# Schematic_01.net
KiCad netlist of a schematic drawn in EAGLE
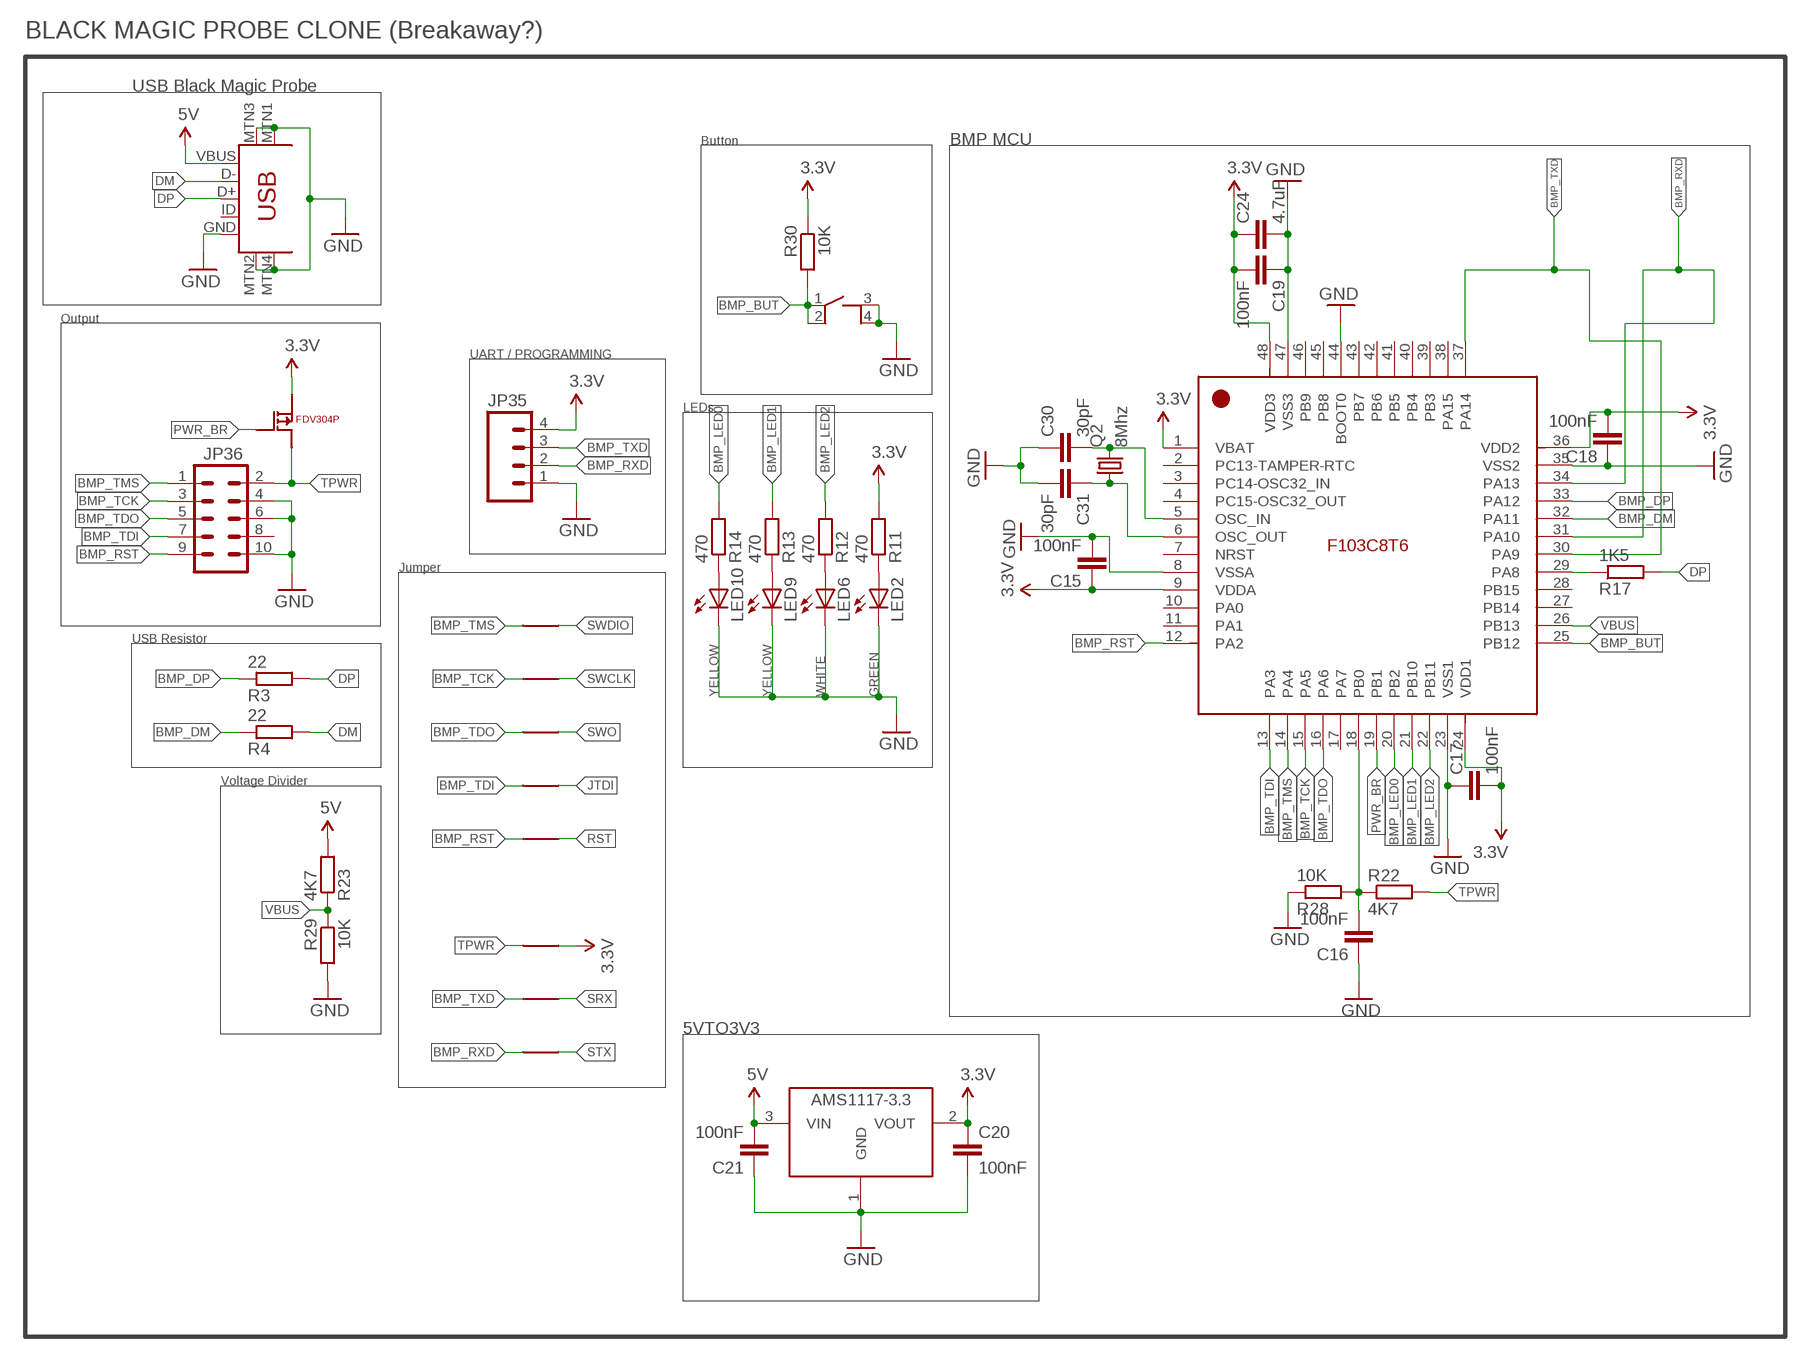
[diagram p0: schematic, sheet 1, part 1 of 2]
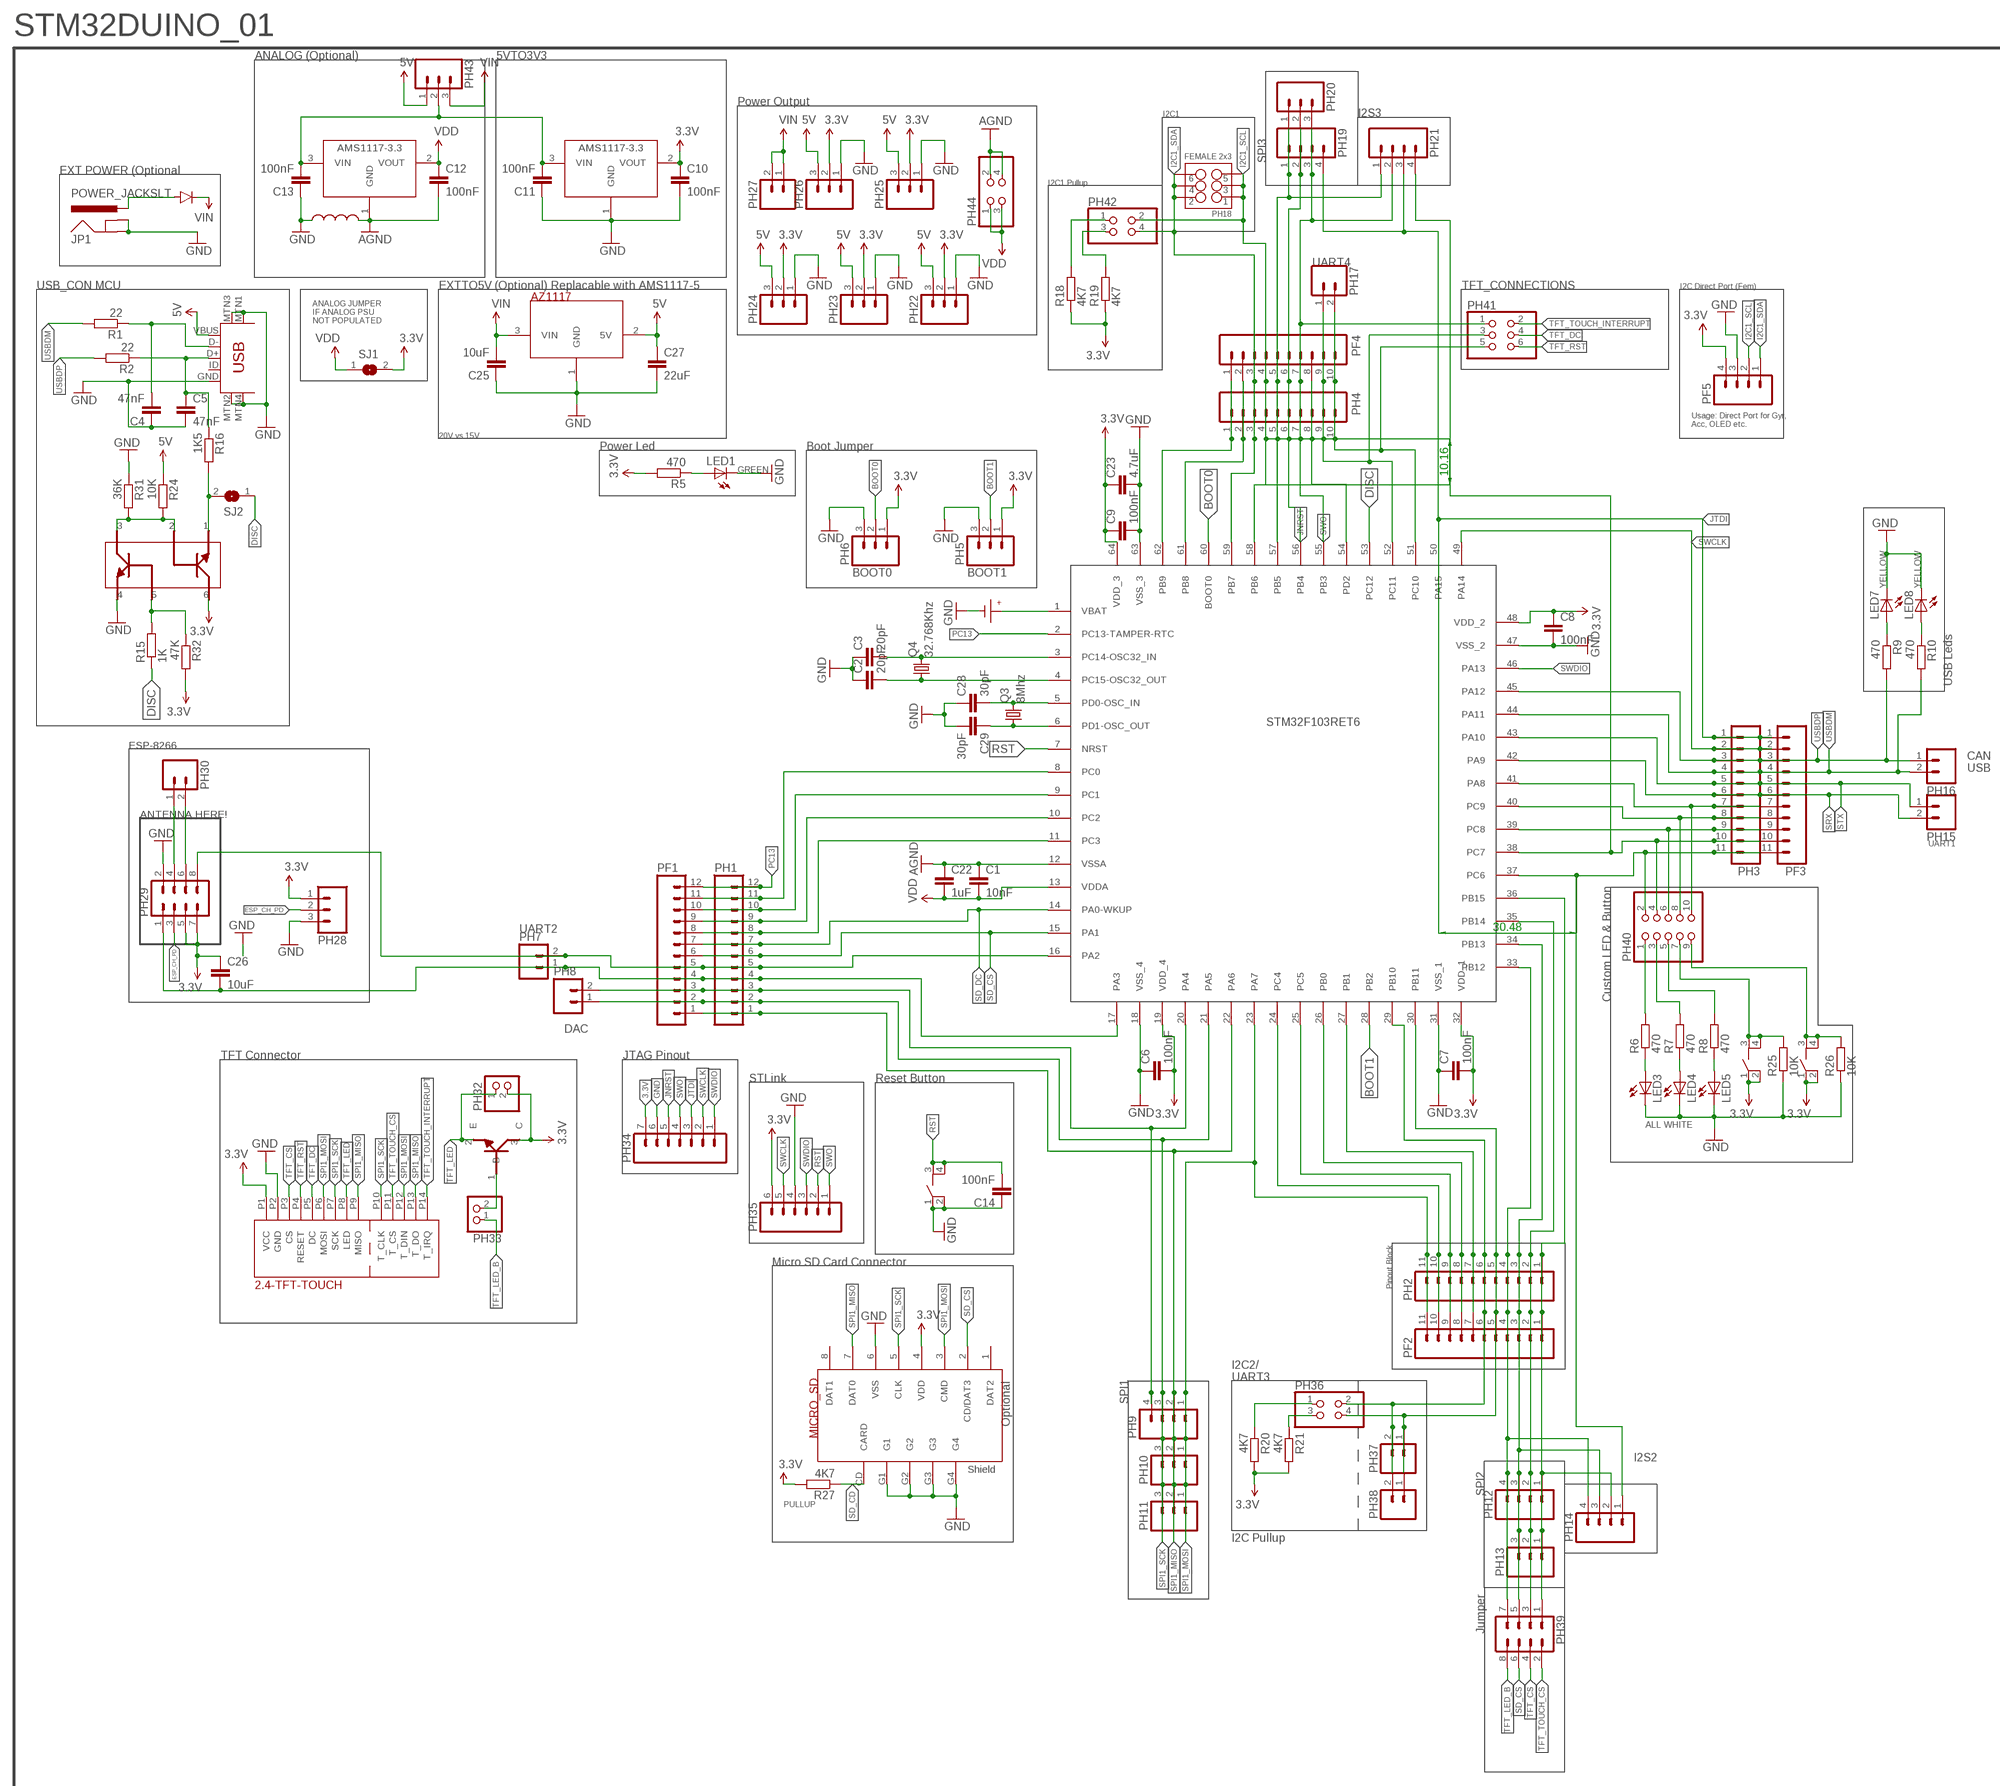
[diagram p1: schematic, sheet 1, part 2 of 2]

(export (version "E")
  (design (tool "Eeschema 10.0.6"))
  (components
    (comp (ref "C1")
      (value "10nF")
      (footprint "eagle-import:C0805K")
      (libsource (lib "eagle-import") (part "C-EUC0805K"))
    )
    (comp (ref "C2")
      (value "20pF")
      (footprint "eagle-import:C0805K")
      (libsource (lib "eagle-import") (part "C-EUC0805K"))
    )
    (comp (ref "C3")
      (value "20pF")
      (footprint "eagle-import:C0805K")
      (libsource (lib "eagle-import") (part "C-EUC0805K"))
    )
    (comp (ref "C4")
      (value "47nF")
      (footprint "eagle-import:C0805K")
      (libsource (lib "eagle-import") (part "C-EUC0805K"))
    )
    (comp (ref "C5")
      (value "47nF")
      (footprint "eagle-import:C0805K")
      (libsource (lib "eagle-import") (part "C-EUC0805K"))
    )
    (comp (ref "C6")
      (value "100nF")
      (footprint "eagle-import:C0805K")
      (libsource (lib "eagle-import") (part "C-EUC0805K"))
    )
    (comp (ref "C7")
      (value "100nF")
      (footprint "eagle-import:C0805K")
      (libsource (lib "eagle-import") (part "C-EUC0805K"))
    )
    (comp (ref "C8")
      (value "100nF")
      (footprint "eagle-import:C0805K")
      (libsource (lib "eagle-import") (part "C-EUC0805K"))
    )
    (comp (ref "C9")
      (value "100nF")
      (footprint "eagle-import:C0805K")
      (libsource (lib "eagle-import") (part "C-EUC0805K"))
    )
    (comp (ref "C10")
      (value "100nF")
      (footprint "eagle-import:C0805K")
      (libsource (lib "eagle-import") (part "C-EUC0805K"))
    )
    (comp (ref "C11")
      (value "100nF")
      (footprint "eagle-import:C0805K")
      (libsource (lib "eagle-import") (part "C-EUC0805K"))
    )
    (comp (ref "C12")
      (value "100nF")
      (footprint "eagle-import:C0805K")
      (libsource (lib "eagle-import") (part "C-EUC0805K"))
    )
    (comp (ref "C13")
      (value "100nF")
      (footprint "eagle-import:C0805K")
      (libsource (lib "eagle-import") (part "C-EUC0805K"))
    )
    (comp (ref "C14")
      (value "100nF")
      (footprint "eagle-import:C0805K")
      (libsource (lib "eagle-import") (part "C-EUC0805K"))
    )
    (comp (ref "C15")
      (value "100nF")
      (footprint "eagle-import:C0805K")
      (libsource (lib "eagle-import") (part "C-EUC0805K"))
    )
    (comp (ref "C16")
      (value "100nF")
      (footprint "eagle-import:C0805K")
      (libsource (lib "eagle-import") (part "C-EUC0805K"))
    )
    (comp (ref "C17")
      (value "100nF")
      (footprint "eagle-import:C0805K")
      (libsource (lib "eagle-import") (part "C-EUC0805K"))
    )
    (comp (ref "C18")
      (value "100nF")
      (footprint "eagle-import:C0805K")
      (libsource (lib "eagle-import") (part "C-EUC0805K"))
    )
    (comp (ref "C19")
      (value "100nF")
      (footprint "eagle-import:C0805K")
      (libsource (lib "eagle-import") (part "C-EUC0805K"))
    )
    (comp (ref "C20")
      (value "100nF")
      (footprint "eagle-import:C0805K")
      (libsource (lib "eagle-import") (part "C-EUC0805K"))
    )
    (comp (ref "C21")
      (value "100nF")
      (footprint "eagle-import:C0805K")
      (libsource (lib "eagle-import") (part "C-EUC0805K"))
    )
    (comp (ref "C22")
      (value "1uF")
      (footprint "eagle-import:C0805K")
      (libsource (lib "eagle-import") (part "C-EUC0805K"))
    )
    (comp (ref "C23")
      (value "4.7uF")
      (footprint "eagle-import:C0805K")
      (libsource (lib "eagle-import") (part "C-EUC0805K"))
    )
    (comp (ref "C24")
      (value "4.7uF")
      (footprint "eagle-import:C0805K")
      (libsource (lib "eagle-import") (part "C-EUC0805K"))
    )
    (comp (ref "C25")
      (value "10uF")
      (footprint "eagle-import:C0805K")
      (libsource (lib "eagle-import") (part "C-EUC0805K"))
    )
    (comp (ref "C26")
      (value "10uF")
      (footprint "eagle-import:C0805K")
      (libsource (lib "eagle-import") (part "C-EUC0805K"))
    )
    (comp (ref "C27")
      (value "22uF")
      (footprint "eagle-import:C0805K")
      (libsource (lib "eagle-import") (part "C-EUC0805K"))
    )
    (comp (ref "C28")
      (value "30pF")
      (footprint "eagle-import:C0805K")
      (libsource (lib "eagle-import") (part "C-EUC0805K"))
    )
    (comp (ref "C29")
      (value "30pF")
      (footprint "eagle-import:C0805K")
      (libsource (lib "eagle-import") (part "C-EUC0805K"))
    )
    (comp (ref "C30")
      (value "30pF")
      (footprint "eagle-import:C0805K")
      (libsource (lib "eagle-import") (part "C-EUC0805K"))
    )
    (comp (ref "C31")
      (value "30pF")
      (footprint "eagle-import:C0805K")
      (libsource (lib "eagle-import") (part "C-EUC0805K"))
    )
    (comp (ref "FB")
      (value "SMD_FERRITE_BEAD")
      (footprint "eagle-import:0805")
      (libsource (lib "eagle-import") (part "SMD_FERRITE_BEAD"))
    )
    (comp (ref "JP1")
      (value "POWER_JACKSLT")
      (footprint "eagle-import:POWER_JACK_SLOT")
      (libsource (lib "eagle-import") (part "POWER_JACKSLT"))
    )
    (comp (ref "JP35")
      (value "M04PTH")
      (footprint "eagle-import:1X04")
      (libsource (lib "eagle-import") (part "M04PTH"))
    )
    (comp (ref "JP36")
      (value "M05X2PTH")
      (footprint "eagle-import:AVR_ICSP")
      (libsource (lib "eagle-import") (part "M05X2PTH"))
    )
    (comp (ref "LED1")
      (value "LEDCHIPLED_0805")
      (footprint "eagle-import:CHIPLED_0805")
      (libsource (lib "eagle-import") (part "LEDCHIPLED_0805"))
    )
    (comp (ref "LED2")
      (value "LEDCHIPLED_1206")
      (footprint "eagle-import:CHIPLED_1206")
      (libsource (lib "eagle-import") (part "LEDCHIPLED_1206"))
    )
    (comp (ref "LED3")
      (value "LEDCHIPLED_0805")
      (footprint "eagle-import:CHIPLED_0805")
      (libsource (lib "eagle-import") (part "LEDCHIPLED_0805"))
    )
    (comp (ref "LED4")
      (value "LEDCHIPLED_0805")
      (footprint "eagle-import:CHIPLED_0805")
      (libsource (lib "eagle-import") (part "LEDCHIPLED_0805"))
    )
    (comp (ref "LED5")
      (value "LEDCHIPLED_0805")
      (footprint "eagle-import:CHIPLED_0805")
      (libsource (lib "eagle-import") (part "LEDCHIPLED_0805"))
    )
    (comp (ref "LED6")
      (value "LEDCHIPLED_1206")
      (footprint "eagle-import:CHIPLED_1206")
      (libsource (lib "eagle-import") (part "LEDCHIPLED_1206"))
    )
    (comp (ref "LED7")
      (value "LEDCHIPLED_0805")
      (footprint "eagle-import:CHIPLED_0805")
      (libsource (lib "eagle-import") (part "LEDCHIPLED_0805"))
    )
    (comp (ref "LED8")
      (value "LEDCHIPLED_0805")
      (footprint "eagle-import:CHIPLED_0805")
      (libsource (lib "eagle-import") (part "LEDCHIPLED_0805"))
    )
    (comp (ref "LED9")
      (value "LEDCHIPLED_1206")
      (footprint "eagle-import:CHIPLED_1206")
      (libsource (lib "eagle-import") (part "LEDCHIPLED_1206"))
    )
    (comp (ref "LED10")
      (value "LEDCHIPLED_1206")
      (footprint "eagle-import:CHIPLED_1206")
      (libsource (lib "eagle-import") (part "LEDCHIPLED_1206"))
    )
    (comp (ref "PF1")
      (value "M12PTH")
      (footprint "eagle-import:1X12")
      (libsource (lib "eagle-import") (part "M12PTH"))
    )
    (comp (ref "PF2")
      (value "M11PTH")
      (footprint "eagle-import:1X11")
      (libsource (lib "eagle-import") (part "M11PTH"))
    )
    (comp (ref "PF3")
      (value "M11PTH")
      (footprint "eagle-import:1X11")
      (libsource (lib "eagle-import") (part "M11PTH"))
    )
    (comp (ref "PF4")
      (value "M10SILK_FEMALE_PTH")
      (footprint "eagle-import:1X10")
      (libsource (lib "eagle-import") (part "M10SILK_FEMALE_PTH"))
    )
    (comp (ref "PF5")
      (value "M04PTH")
      (footprint "eagle-import:1X04")
      (libsource (lib "eagle-import") (part "M04PTH"))
    )
    (comp (ref "PH1")
      (value "M12PTH")
      (footprint "eagle-import:1X12")
      (libsource (lib "eagle-import") (part "M12PTH"))
    )
    (comp (ref "PH2")
      (value "M11PTH")
      (footprint "eagle-import:1X11")
      (libsource (lib "eagle-import") (part "M11PTH"))
    )
    (comp (ref "PH3")
      (value "M11PTH")
      (footprint "eagle-import:1X11")
      (libsource (lib "eagle-import") (part "M11PTH"))
    )
    (comp (ref "PH4")
      (value "M10SILK_FEMALE_PTH")
      (footprint "eagle-import:1X10")
      (libsource (lib "eagle-import") (part "M10SILK_FEMALE_PTH"))
    )
    (comp (ref "PH5")
      (value "M03PTH")
      (footprint "eagle-import:1X03")
      (libsource (lib "eagle-import") (part "M03PTH"))
    )
    (comp (ref "PH6")
      (value "M03PTH")
      (footprint "eagle-import:1X03")
      (libsource (lib "eagle-import") (part "M03PTH"))
    )
    (comp (ref "PH7")
      (value "M02PTH")
      (footprint "eagle-import:1X02")
      (libsource (lib "eagle-import") (part "M02PTH"))
    )
    (comp (ref "PH8")
      (value "M02PTH")
      (footprint "eagle-import:1X02")
      (libsource (lib "eagle-import") (part "M02PTH"))
    )
    (comp (ref "PH9")
      (value "M04PTH")
      (footprint "eagle-import:1X04")
      (libsource (lib "eagle-import") (part "M04PTH"))
    )
    (comp (ref "PH10")
      (value "M03PTH")
      (footprint "eagle-import:1X03")
      (libsource (lib "eagle-import") (part "M03PTH"))
    )
    (comp (ref "PH11")
      (value "M03PTH")
      (footprint "eagle-import:1X03")
      (libsource (lib "eagle-import") (part "M03PTH"))
    )
    (comp (ref "PH12")
      (value "M04PTH")
      (footprint "eagle-import:1X04")
      (libsource (lib "eagle-import") (part "M04PTH"))
    )
    (comp (ref "PH13")
      (value "M03PTH")
      (footprint "eagle-import:1X03")
      (libsource (lib "eagle-import") (part "M03PTH"))
    )
    (comp (ref "PH14")
      (value "M04PTH")
      (footprint "eagle-import:1X04")
      (libsource (lib "eagle-import") (part "M04PTH"))
    )
    (comp (ref "PH15")
      (value "M02PTH")
      (footprint "eagle-import:1X02")
      (libsource (lib "eagle-import") (part "M02PTH"))
    )
    (comp (ref "PH16")
      (value "M02PTH")
      (footprint "eagle-import:1X02")
      (libsource (lib "eagle-import") (part "M02PTH"))
    )
    (comp (ref "PH17")
      (value "M02PTH")
      (footprint "eagle-import:1X02")
      (libsource (lib "eagle-import") (part "M02PTH"))
    )
    (comp (ref "PH18")
      (value "FEMALE 2x3")
      (footprint "eagle-import:2X3")
      (libsource (lib "eagle-import") (part "M03X2FEMALE"))
    )
    (comp (ref "PH19")
      (value "M04PTH")
      (footprint "eagle-import:1X04")
      (libsource (lib "eagle-import") (part "M04PTH"))
    )
    (comp (ref "PH20")
      (value "M03PTH")
      (footprint "eagle-import:1X03")
      (libsource (lib "eagle-import") (part "M03PTH"))
    )
    (comp (ref "PH21")
      (value "M04PTH")
      (footprint "eagle-import:1X04")
      (libsource (lib "eagle-import") (part "M04PTH"))
    )
    (comp (ref "PH22")
      (value "M03PTH")
      (footprint "eagle-import:1X03")
      (libsource (lib "eagle-import") (part "M03PTH"))
    )
    (comp (ref "PH23")
      (value "M03PTH")
      (footprint "eagle-import:1X03")
      (libsource (lib "eagle-import") (part "M03PTH"))
    )
    (comp (ref "PH24")
      (value "M03PTH")
      (footprint "eagle-import:1X03")
      (libsource (lib "eagle-import") (part "M03PTH"))
    )
    (comp (ref "PH25")
      (value "M03PTH")
      (footprint "eagle-import:1X03")
      (libsource (lib "eagle-import") (part "M03PTH"))
    )
    (comp (ref "PH26")
      (value "M03PTH")
      (footprint "eagle-import:1X03")
      (libsource (lib "eagle-import") (part "M03PTH"))
    )
    (comp (ref "PH27")
      (value "M02PTH")
      (footprint "eagle-import:1X02")
      (libsource (lib "eagle-import") (part "M02PTH"))
    )
    (comp (ref "PH28")
      (value "M03PTH")
      (footprint "eagle-import:1X03")
      (libsource (lib "eagle-import") (part "M03PTH"))
    )
    (comp (ref "PH29")
      (value "M04X2")
      (footprint "eagle-import:2X4")
      (libsource (lib "eagle-import") (part "M04X2"))
    )
    (comp (ref "PH30")
      (value "M02PTH")
      (footprint "eagle-import:1X02")
      (libsource (lib "eagle-import") (part "M02PTH"))
    )
    (comp (ref "PH31")
      (value "TFT-TOUCH")
      (footprint "eagle-import:TFT-TOUCH")
      (libsource (lib "eagle-import") (part "TFT-TOUCH"))
    )
    (comp (ref "PH32")
      (value "PINHD-1X2")
      (footprint "eagle-import:1X02")
      (libsource (lib "eagle-import") (part "PINHD-1X2"))
    )
    (comp (ref "PH33")
      (value "PINHD-1X2")
      (footprint "eagle-import:1X02")
      (libsource (lib "eagle-import") (part "PINHD-1X2"))
    )
    (comp (ref "PH34")
      (value "M07")
      (footprint "eagle-import:1X07")
      (libsource (lib "eagle-import") (part "M07"))
    )
    (comp (ref "PH35")
      (value "M06SILK_FEMALE_PTH")
      (footprint "eagle-import:1X06")
      (libsource (lib "eagle-import") (part "M06SILK_FEMALE_PTH"))
    )
    (comp (ref "PH36")
      (value "PINHD-2X2")
      (footprint "eagle-import:2X02")
      (libsource (lib "eagle-import") (part "PINHD-2X2"))
    )
    (comp (ref "PH37")
      (value "M02PTH")
      (footprint "eagle-import:1X02")
      (libsource (lib "eagle-import") (part "M02PTH"))
    )
    (comp (ref "PH38")
      (value "M02PTH")
      (footprint "eagle-import:1X02")
      (libsource (lib "eagle-import") (part "M02PTH"))
    )
    (comp (ref "PH39")
      (value "M04X2")
      (footprint "eagle-import:2X4")
      (libsource (lib "eagle-import") (part "M04X2"))
    )
    (comp (ref "PH40")
      (value "PINHD-2X5")
      (footprint "eagle-import:2X05")
      (libsource (lib "eagle-import") (part "PINHD-2X5"))
    )
    (comp (ref "PH41")
      (value "PINHD-2X3")
      (footprint "eagle-import:2X03")
      (libsource (lib "eagle-import") (part "PINHD-2X3"))
    )
    (comp (ref "PH42")
      (value "PINHD-2X2")
      (footprint "eagle-import:2X02")
      (libsource (lib "eagle-import") (part "PINHD-2X2"))
    )
    (comp (ref "PH43")
      (value "M03PTH")
      (footprint "eagle-import:1X03")
      (libsource (lib "eagle-import") (part "M03PTH"))
    )
    (comp (ref "PH44")
      (value "PINHD-2X2")
      (footprint "eagle-import:2X02")
      (libsource (lib "eagle-import") (part "PINHD-2X2"))
    )
    (comp (ref "Q2")
      (value "8Mhz")
      (footprint "eagle-import:SM49")
      (libsource (lib "eagle-import") (part "CRYSTALSM49"))
    )
    (comp (ref "Q3")
      (value "8Mhz")
      (footprint "eagle-import:SM49")
      (libsource (lib "eagle-import") (part "CRYSTALSM49"))
    )
    (comp (ref "Q4")
      (value "32.768Khz")
      (footprint "eagle-import:MC-306")
      (fields (field (name "MPN") "MC-306 60.0KHZ  100PPM ,12.5PF"))
      (libsource (lib "eagle-import") (part "MC-306"))
    )
    (comp (ref "R1")
      (value "22")
      (footprint "eagle-import:R0805")
      (libsource (lib "eagle-import") (part "R-EU_R0805"))
    )
    (comp (ref "R2")
      (value "22")
      (footprint "eagle-import:R0805")
      (libsource (lib "eagle-import") (part "R-EU_R0805"))
    )
    (comp (ref "R3")
      (value "22")
      (footprint "eagle-import:R0805")
      (libsource (lib "eagle-import") (part "R-EU_R0805"))
    )
    (comp (ref "R4")
      (value "22")
      (footprint "eagle-import:R0805")
      (libsource (lib "eagle-import") (part "R-EU_R0805"))
    )
    (comp (ref "R5")
      (value "470")
      (footprint "eagle-import:R0805")
      (libsource (lib "eagle-import") (part "R-EU_R0805"))
    )
    (comp (ref "R6")
      (value "470")
      (footprint "eagle-import:R0805")
      (libsource (lib "eagle-import") (part "R-EU_R0805"))
    )
    (comp (ref "R7")
      (value "470")
      (footprint "eagle-import:R0805")
      (libsource (lib "eagle-import") (part "R-EU_R0805"))
    )
    (comp (ref "R8")
      (value "470")
      (footprint "eagle-import:R0805")
      (libsource (lib "eagle-import") (part "R-EU_R0805"))
    )
    (comp (ref "R9")
      (value "470")
      (footprint "eagle-import:R0805")
      (libsource (lib "eagle-import") (part "R-EU_R0805"))
    )
    (comp (ref "R10")
      (value "470")
      (footprint "eagle-import:R0805")
      (libsource (lib "eagle-import") (part "R-EU_R0805"))
    )
    (comp (ref "R11")
      (value "470")
      (footprint "eagle-import:R0805")
      (libsource (lib "eagle-import") (part "R-EU_R0805"))
    )
    (comp (ref "R12")
      (value "470")
      (footprint "eagle-import:R0805")
      (libsource (lib "eagle-import") (part "R-EU_R0805"))
    )
    (comp (ref "R13")
      (value "470")
      (footprint "eagle-import:R0805")
      (libsource (lib "eagle-import") (part "R-EU_R0805"))
    )
    (comp (ref "R14")
      (value "470")
      (footprint "eagle-import:R0805")
      (libsource (lib "eagle-import") (part "R-EU_R0805"))
    )
    (comp (ref "R15")
      (value "1K")
      (footprint "eagle-import:R0805")
      (libsource (lib "eagle-import") (part "R-EU_R0805"))
    )
    (comp (ref "R16")
      (value "1K5")
      (footprint "eagle-import:R0805")
      (libsource (lib "eagle-import") (part "R-EU_R0805"))
    )
    (comp (ref "R17")
      (value "1K5")
      (footprint "eagle-import:R0805")
      (libsource (lib "eagle-import") (part "R-EU_R0805"))
    )
    (comp (ref "R18")
      (value "4K7")
      (footprint "eagle-import:R0805")
      (libsource (lib "eagle-import") (part "R-EU_R0805"))
    )
    (comp (ref "R19")
      (value "4K7")
      (footprint "eagle-import:R0805")
      (libsource (lib "eagle-import") (part "R-EU_R0805"))
    )
    (comp (ref "R20")
      (value "4K7")
      (footprint "eagle-import:R0805")
      (libsource (lib "eagle-import") (part "R-EU_R0805"))
    )
    (comp (ref "R21")
      (value "4K7")
      (footprint "eagle-import:R0805")
      (libsource (lib "eagle-import") (part "R-EU_R0805"))
    )
    (comp (ref "R22")
      (value "4K7")
      (footprint "eagle-import:R0805")
      (libsource (lib "eagle-import") (part "R-EU_R0805"))
    )
    (comp (ref "R23")
      (value "4K7")
      (footprint "eagle-import:R0805")
      (libsource (lib "eagle-import") (part "R-EU_R0805"))
    )
    (comp (ref "R24")
      (value "10K")
      (footprint "eagle-import:R0805")
      (libsource (lib "eagle-import") (part "R-EU_R0805"))
    )
    (comp (ref "R25")
      (value "10K")
      (footprint "eagle-import:R0805")
      (libsource (lib "eagle-import") (part "R-EU_R0805"))
    )
    (comp (ref "R26")
      (value "10K")
      (footprint "eagle-import:R0805")
      (libsource (lib "eagle-import") (part "R-EU_R0805"))
    )
    (comp (ref "R27")
      (value "4K7")
      (footprint "eagle-import:R0805")
      (libsource (lib "eagle-import") (part "R-EU_R0805"))
    )
    (comp (ref "R28")
      (value "10K")
      (footprint "eagle-import:R0805")
      (libsource (lib "eagle-import") (part "R-EU_R0805"))
    )
    (comp (ref "R29")
      (value "10K")
      (footprint "eagle-import:R0805")
      (libsource (lib "eagle-import") (part "R-EU_R0805"))
    )
    (comp (ref "R30")
      (value "10K")
      (footprint "eagle-import:R0805")
      (libsource (lib "eagle-import") (part "R-EU_R0805"))
    )
    (comp (ref "R31")
      (value "36K")
      (footprint "eagle-import:R0805")
      (libsource (lib "eagle-import") (part "R-EU_R0805"))
    )
    (comp (ref "R32")
      (value "47K")
      (footprint "eagle-import:R0805")
      (libsource (lib "eagle-import") (part "R-EU_R0805"))
    )
    (comp (ref "SJ1") (value "SJ") (footprint "eagle-import:SJ") (libsource (lib "eagle-import") (part "SJ")))
    (comp (ref "SJ2") (value "SJ") (footprint "eagle-import:SJ") (libsource (lib "eagle-import") (part "SJ")))
    (comp (ref "U$1")
      (value "BRIDGE")
      (footprint "eagle-import:BRIDGE")
      (libsource (lib "eagle-import") (part "BRIDGE"))
    )
    (comp (ref "U$2")
      (value "SMD_BUT_6MM")
      (footprint "eagle-import:SMD_BUT_6MM")
      (libsource (lib "eagle-import") (part "SMD_BUT_6MM"))
    )
    (comp (ref "U$4")
      (value "BRIDGE")
      (footprint "eagle-import:BRIDGE")
      (libsource (lib "eagle-import") (part "BRIDGE"))
    )
    (comp (ref "U$5")
      (value "SMD_BUT_6MM")
      (footprint "eagle-import:SMD_BUT_6MM")
      (libsource (lib "eagle-import") (part "SMD_BUT_6MM"))
    )
    (comp (ref "U$6")
      (value "CR2025_BATHOLDER_PTH")
      (footprint "eagle-import:CR2025HOLDER_PTH")
      (libsource (lib "eagle-import") (part "CR2025_BATHOLDER_PTH"))
    )
    (comp (ref "U$7")
      (value "SD_CARD")
      (footprint "eagle-import:SD_CARD")
      (libsource (lib "eagle-import") (part "SD_CARD"))
    )
    (comp (ref "U$8")
      (value "SMD_BUT_6MM")
      (footprint "eagle-import:SMD_BUT_6MM")
      (libsource (lib "eagle-import") (part "SMD_BUT_6MM"))
    )
    (comp (ref "U$9")
      (value "SMD_BUT_6MM")
      (footprint "eagle-import:SMD_BUT_6MM")
      (libsource (lib "eagle-import") (part "SMD_BUT_6MM"))
    )
    (comp (ref "U$10")
      (value "BRIDGE")
      (footprint "eagle-import:BRIDGE")
      (libsource (lib "eagle-import") (part "BRIDGE"))
    )
    (comp (ref "U$15")
      (value "BRIDGE")
      (footprint "eagle-import:BRIDGE")
      (libsource (lib "eagle-import") (part "BRIDGE"))
    )
    (comp (ref "U$16")
      (value "BRIDGE")
      (footprint "eagle-import:BRIDGE")
      (libsource (lib "eagle-import") (part "BRIDGE"))
    )
    (comp (ref "U$17")
      (value "BRIDGE")
      (footprint "eagle-import:BRIDGE")
      (libsource (lib "eagle-import") (part "BRIDGE"))
    )
    (comp (ref "U$18")
      (value "BRIDGE")
      (footprint "eagle-import:BRIDGE")
      (libsource (lib "eagle-import") (part "BRIDGE"))
    )
    (comp (ref "U$19")
      (value "BRIDGE")
      (footprint "eagle-import:BRIDGE")
      (libsource (lib "eagle-import") (part "BRIDGE"))
    )
    (comp (ref "U$25")
      (value "1N4007_SMD")
      (footprint "eagle-import:DO-214AC")
      (libsource (lib "eagle-import") (part "1N4007_SMD"))
    )
    (comp (ref "U1")
      (value "STM32F103RET6")
      (footprint "eagle-import:LQFP64_0.5MMPP")
      (libsource (lib "eagle-import") (part "STM32F103RET6"))
    )
    (comp (ref "U2")
      (value "STM32F103C8T6")
      (footprint "eagle-import:LQFP48_7X7MM_0.5MMPP")
      (libsource (lib "eagle-import") (part "STM32F103C8T6"))
    )
    (comp (ref "U3")
      (value "AMS1117-3.3")
      (footprint "eagle-import:SOT223")
      (libsource (lib "eagle-import") (part "AMS1117-3.3"))
    )
    (comp (ref "U4")
      (value "AMS1117-3.3")
      (footprint "eagle-import:SOT223")
      (libsource (lib "eagle-import") (part "AMS1117-3.3"))
    )
    (comp (ref "U5")
      (value "AZ1117-5.0")
      (footprint "eagle-import:SOT223")
      (libsource (lib "eagle-import") (part "AZ1117-5.0"))
    )
    (comp (ref "U6")
      (value "AMS1117-3.3")
      (footprint "eagle-import:SOT223")
      (libsource (lib "eagle-import") (part "AMS1117-3.3"))
    )
    (comp (ref "U7")
      (value "MBT3904DW1T1G")
      (footprint "eagle-import:SOT236")
      (libsource (lib "eagle-import") (part "MBT3904DW1T1G"))
    )
    (comp (ref "U8")
      (value "BC846A")
      (footprint "eagle-import:SOT23-3")
      (libsource (lib "eagle-import") (part "BC846A"))
    )
    (comp (ref "U9")
      (value "FDV304P")
      (footprint "eagle-import:SOT23-3")
      (libsource (lib "eagle-import") (part "FDV304P"))
    )
    (comp (ref "USB1")
      (value "USB-MINIB-5PIN")
      (footprint "eagle-import:USB-MINIB")
      (libsource (lib "eagle-import") (part "USB-MINIB-5PIN"))
    )
    (comp (ref "USB2")
      (value "USB-MINIB-5PIN")
      (footprint "eagle-import:USB-MINIB")
      (libsource (lib "eagle-import") (part "USB-MINIB-5PIN"))
    )
  )
  (nets
    (net (code "1") (name "3.3V") (class "Default")
      (node (ref "C10") (pin "1") (pinfunction "1_1") (pintype "passive"))
      (node (ref "C15") (pin "1") (pinfunction "1_1") (pintype "passive"))
      (node (ref "C17") (pin "2") (pinfunction "2_2") (pintype "passive"))
      (node (ref "C18") (pin "2") (pinfunction "2_2") (pintype "passive"))
      (node (ref "C19") (pin "2") (pinfunction "2_2") (pintype "passive"))
      (node (ref "C20") (pin "1") (pinfunction "1_1") (pintype "passive"))
      (node (ref "C23") (pin "1") (pinfunction "1_1") (pintype "passive"))
      (node (ref "C24") (pin "1") (pinfunction "1_1") (pintype "passive"))
      (node (ref "C26") (pin "1") (pinfunction "1_1") (pintype "passive"))
      (node (ref "C6") (pin "2") (pinfunction "2_2") (pintype "passive"))
      (node (ref "C7") (pin "2") (pinfunction "2_2") (pintype "passive"))
      (node (ref "C8") (pin "1") (pinfunction "1_1") (pintype "passive"))
      (node (ref "C9") (pin "1") (pinfunction "1_1") (pintype "passive"))
      (node (ref "JP35") (pin "4") (pinfunction "4_4") (pintype "passive"))
      (node (ref "PF5") (pin "4") (pinfunction "4_4") (pintype "passive"))
      (node (ref "PH22") (pin "2") (pinfunction "2_2") (pintype "passive"))
      (node (ref "PH23") (pin "2") (pinfunction "2_2") (pintype "passive"))
      (node (ref "PH24") (pin "2") (pinfunction "2_2") (pintype "passive"))
      (node (ref "PH25") (pin "2") (pinfunction "2_2") (pintype "passive"))
      (node (ref "PH26") (pin "2") (pinfunction "2_2") (pintype "passive"))
      (node (ref "PH28") (pin "1") (pinfunction "1_1") (pintype "passive"))
      (node (ref "PH29") (pin "5") (pinfunction "5_5") (pintype "passive"))
      (node (ref "PH29") (pin "7") (pinfunction "7_7") (pintype "passive"))
      (node (ref "PH31") (pin "P1") (pinfunction "VCC_P1") (pintype "bidirectional"))
      (node (ref "PH32") (pin "2") (pinfunction "2_2") (pintype "passive"))
      (node (ref "PH34") (pin "7") (pinfunction "7_7") (pintype "passive"))
      (node (ref "PH35") (pin "6") (pinfunction "6_6") (pintype "passive"))
      (node (ref "PH5") (pin "1") (pinfunction "1_1") (pintype "passive"))
      (node (ref "PH6") (pin "1") (pinfunction "1_1") (pintype "passive"))
      (node (ref "R11") (pin "2") (pinfunction "2_2") (pintype "passive"))
      (node (ref "R18") (pin "1") (pinfunction "1_1") (pintype "passive"))
      (node (ref "R19") (pin "1") (pinfunction "1_1") (pintype "passive"))
      (node (ref "R20") (pin "2") (pinfunction "2_2") (pintype "passive"))
      (node (ref "R21") (pin "2") (pinfunction "2_2") (pintype "passive"))
      (node (ref "R27") (pin "2") (pinfunction "2_2") (pintype "passive"))
      (node (ref "R30") (pin "1") (pinfunction "1_1") (pintype "passive"))
      (node (ref "R32") (pin "2") (pinfunction "2_2") (pintype "passive"))
      (node (ref "R5") (pin "2") (pinfunction "2_2") (pintype "passive"))
      (node (ref "SJ1") (pin "2") (pinfunction "2_2") (pintype "passive"))
      (node (ref "U$10") (pin "P$2") (pinfunction "P$2_P$2") (pintype "bidirectional"))
      (node (ref "U$7") (pin "4") (pinfunction "VDD_4") (pintype "bidirectional"))
      (node (ref "U$8") (pin "1") (pinfunction "P1_1") (pintype "bidirectional"))
      (node (ref "U$8") (pin "2") (pinfunction "P2_2") (pintype "bidirectional"))
      (node (ref "U$9") (pin "1") (pinfunction "P1_1") (pintype "bidirectional"))
      (node (ref "U$9") (pin "2") (pinfunction "P2_2") (pintype "bidirectional"))
      (node (ref "U1") (pin "19") (pinfunction "VDD_4_19") (pintype "bidirectional"))
      (node (ref "U1") (pin "32") (pinfunction "VDD_1_32") (pintype "bidirectional"))
      (node (ref "U1") (pin "48") (pinfunction "VDD_2_48") (pintype "bidirectional"))
      (node (ref "U1") (pin "64") (pinfunction "VDD_3_64") (pintype "bidirectional"))
      (node (ref "U2") (pin "1") (pinfunction "VBAT_1") (pintype "bidirectional"))
      (node (ref "U2") (pin "24") (pinfunction "VDD1_24") (pintype "bidirectional"))
      (node (ref "U2") (pin "36") (pinfunction "VDD2_36") (pintype "bidirectional"))
      (node (ref "U2") (pin "48") (pinfunction "VDD3_48") (pintype "bidirectional"))
      (node (ref "U2") (pin "9") (pinfunction "VDDA_9") (pintype "bidirectional"))
      (node (ref "U3") (pin "2") (pinfunction "VOUT_2") (pintype "bidirectional"))
      (node (ref "U6") (pin "2") (pinfunction "VOUT_2") (pintype "bidirectional"))
      (node (ref "U7") (pin "6") (pinfunction "6_6") (pintype "bidirectional"))
      (node (ref "U8") (pin "3") (pinfunction "C_3") (pintype "bidirectional"))
      (node (ref "U9") (pin "2") (pinfunction "S_2") (pintype "bidirectional"))
    )
    (net (code "2") (name "5V") (class "Default")
      (node (ref "C21") (pin "2") (pinfunction "2_2") (pintype "passive"))
      (node (ref "C27") (pin "1") (pinfunction "1_1") (pintype "passive"))
      (node (ref "PH22") (pin "3") (pinfunction "3_3") (pintype "passive"))
      (node (ref "PH23") (pin "3") (pinfunction "3_3") (pintype "passive"))
      (node (ref "PH24") (pin "3") (pinfunction "3_3") (pintype "passive"))
      (node (ref "PH25") (pin "3") (pinfunction "3_3") (pintype "passive"))
      (node (ref "PH26") (pin "3") (pinfunction "3_3") (pintype "passive"))
      (node (ref "PH43") (pin "1") (pinfunction "1_1") (pintype "passive"))
      (node (ref "R23") (pin "2") (pinfunction "2_2") (pintype "passive"))
      (node (ref "R24") (pin "1") (pinfunction "1_1") (pintype "passive"))
      (node (ref "U5") (pin "2") (pinfunction "5V_2") (pintype "bidirectional"))
      (node (ref "U6") (pin "3") (pinfunction "VIN_3") (pintype "bidirectional"))
      (node (ref "USB1") (pin "VBUS") (pinfunction "VBUS_VBUS") (pintype "bidirectional"))
      (node (ref "USB2") (pin "VBUS") (pinfunction "VBUS_VBUS") (pintype "bidirectional"))
    )
    (net (code "3") (name "AGND") (class "Default")
      (node (ref "C1") (pin "1") (pinfunction "1_1") (pintype "passive"))
      (node (ref "C12") (pin "2") (pinfunction "2_2") (pintype "passive"))
      (node (ref "C22") (pin "1") (pinfunction "1_1") (pintype "passive"))
      (node (ref "FB") (pin "P$4") (pinfunction "2_P$4") (pintype "bidirectional"))
      (node (ref "PH44") (pin "2") (pinfunction "2_2") (pintype "passive"))
      (node (ref "PH44") (pin "4") (pinfunction "4_4") (pintype "passive"))
      (node (ref "U1") (pin "12") (pinfunction "VSSA_12") (pintype "bidirectional"))
      (node (ref "U4") (pin "1") (pinfunction "GND_1") (pintype "bidirectional"))
    )
    (net (code "4") (name "BMP_BUT") (class "Default")
      (node (ref "R30") (pin "2") (pinfunction "2_2") (pintype "passive"))
      (node (ref "U$2") (pin "1") (pinfunction "P1_1") (pintype "bidirectional"))
      (node (ref "U$2") (pin "2") (pinfunction "P2_2") (pintype "bidirectional"))
      (node (ref "U2") (pin "25") (pinfunction "PB12_25") (pintype "bidirectional"))
    )
    (net (code "5") (name "BMP_DM") (class "Default")
      (node (ref "R4") (pin "1") (pinfunction "1_1") (pintype "passive"))
      (node (ref "U2") (pin "32") (pinfunction "PA11_32") (pintype "bidirectional"))
    )
    (net (code "6") (name "BMP_DP") (class "Default")
      (node (ref "R3") (pin "1") (pinfunction "1_1") (pintype "passive"))
      (node (ref "U2") (pin "33") (pinfunction "PA12_33") (pintype "bidirectional"))
    )
    (net (code "7") (name "BMP_LED0") (class "Default")
      (node (ref "R14") (pin "2") (pinfunction "2_2") (pintype "passive"))
      (node (ref "U2") (pin "20") (pinfunction "PB2_20") (pintype "bidirectional"))
    )
    (net (code "8") (name "BMP_LED1") (class "Default")
      (node (ref "R13") (pin "2") (pinfunction "2_2") (pintype "passive"))
      (node (ref "U2") (pin "21") (pinfunction "PB10_21") (pintype "bidirectional"))
    )
    (net (code "9") (name "BMP_LED2") (class "Default")
      (node (ref "R12") (pin "2") (pinfunction "2_2") (pintype "passive"))
      (node (ref "U2") (pin "22") (pinfunction "PB11_22") (pintype "bidirectional"))
    )
    (net (code "10") (name "BMP_RST") (class "Default")
      (node (ref "JP36") (pin "9") (pinfunction "9_9") (pintype "passive"))
      (node (ref "U$15") (pin "P$1") (pinfunction "P$1_P$1") (pintype "bidirectional"))
      (node (ref "U2") (pin "12") (pinfunction "PA2_12") (pintype "bidirectional"))
    )
    (net (code "11") (name "BMP_RXD") (class "Default")
      (node (ref "JP35") (pin "2") (pinfunction "2_2") (pintype "passive"))
      (node (ref "U$1") (pin "P$1") (pinfunction "P$1_P$1") (pintype "bidirectional"))
      (node (ref "U2") (pin "31") (pinfunction "PA10_31") (pintype "bidirectional"))
      (node (ref "U2") (pin "34") (pinfunction "PA13_34") (pintype "bidirectional"))
    )
    (net (code "12") (name "BMP_TCK") (class "Default")
      (node (ref "JP36") (pin "3") (pinfunction "3_3") (pintype "passive"))
      (node (ref "U$18") (pin "P$1") (pinfunction "P$1_P$1") (pintype "bidirectional"))
      (node (ref "U2") (pin "15") (pinfunction "PA5_15") (pintype "bidirectional"))
    )
    (net (code "13") (name "BMP_TDI") (class "Default")
      (node (ref "JP36") (pin "7") (pinfunction "7_7") (pintype "passive"))
      (node (ref "U$16") (pin "P$1") (pinfunction "P$1_P$1") (pintype "bidirectional"))
      (node (ref "U2") (pin "13") (pinfunction "PA3_13") (pintype "bidirectional"))
    )
    (net (code "14") (name "BMP_TDO") (class "Default")
      (node (ref "JP36") (pin "5") (pinfunction "5_5") (pintype "passive"))
      (node (ref "U$17") (pin "P$1") (pinfunction "P$1_P$1") (pintype "bidirectional"))
      (node (ref "U2") (pin "16") (pinfunction "PA6_16") (pintype "bidirectional"))
    )
    (net (code "15") (name "BMP_TMS") (class "Default")
      (node (ref "JP36") (pin "1") (pinfunction "1_1") (pintype "passive"))
      (node (ref "U$19") (pin "P$1") (pinfunction "P$1_P$1") (pintype "bidirectional"))
      (node (ref "U2") (pin "14") (pinfunction "PA4_14") (pintype "bidirectional"))
    )
    (net (code "16") (name "BMP_TXD") (class "Default")
      (node (ref "JP35") (pin "3") (pinfunction "3_3") (pintype "passive"))
      (node (ref "U$4") (pin "P$1") (pinfunction "P$1_P$1") (pintype "bidirectional"))
      (node (ref "U2") (pin "30") (pinfunction "PA9_30") (pintype "bidirectional"))
      (node (ref "U2") (pin "37") (pinfunction "PA14_37") (pintype "bidirectional"))
    )
    (net (code "17") (name "BOOT0") (class "Default")
      (node (ref "PH6") (pin "2") (pinfunction "2_2") (pintype "passive"))
      (node (ref "U1") (pin "60") (pinfunction "BOOT0_60") (pintype "bidirectional"))
    )
    (net (code "18") (name "BOOT1") (class "Default")
      (node (ref "PH5") (pin "2") (pinfunction "2_2") (pintype "passive"))
      (node (ref "U1") (pin "28") (pinfunction "PB2_28") (pintype "bidirectional"))
    )
    (net (code "19") (name "DISC") (class "Default")
      (node (ref "R15") (pin "1") (pinfunction "1_1") (pintype "passive"))
      (node (ref "SJ2") (pin "1") (pinfunction "1_1") (pintype "passive"))
      (node (ref "U1") (pin "53") (pinfunction "PC12_53") (pintype "bidirectional"))
    )
    (net (code "20") (name "DM") (class "Default")
      (node (ref "R4") (pin "2") (pinfunction "2_2") (pintype "passive"))
      (node (ref "USB2") (pin "D-") (pinfunction "D-_D-") (pintype "bidirectional"))
    )
    (net (code "21") (name "DP") (class "Default")
      (node (ref "R17") (pin "2") (pinfunction "2_2") (pintype "passive"))
      (node (ref "R3") (pin "2") (pinfunction "2_2") (pintype "passive"))
      (node (ref "USB2") (pin "D+") (pinfunction "D+_D+") (pintype "bidirectional"))
    )
    (net (code "22") (name "ESP_CH_PD") (class "Default")
      (node (ref "PH28") (pin "2") (pinfunction "2_2") (pintype "passive"))
      (node (ref "PH29") (pin "3") (pinfunction "3_3") (pintype "passive"))
    )
    (net (code "23") (name "GND") (class "Default")
      (node (ref "C10") (pin "2") (pinfunction "2_2") (pintype "passive"))
      (node (ref "C11") (pin "1") (pinfunction "1_1") (pintype "passive"))
      (node (ref "C13") (pin "1") (pinfunction "1_1") (pintype "passive"))
      (node (ref "C14") (pin "1") (pinfunction "1_1") (pintype "passive"))
      (node (ref "C15") (pin "2") (pinfunction "2_2") (pintype "passive"))
      (node (ref "C16") (pin "1") (pinfunction "1_1") (pintype "passive"))
      (node (ref "C17") (pin "1") (pinfunction "1_1") (pintype "passive"))
      (node (ref "C18") (pin "1") (pinfunction "1_1") (pintype "passive"))
      (node (ref "C19") (pin "1") (pinfunction "1_1") (pintype "passive"))
      (node (ref "C2") (pin "1") (pinfunction "1_1") (pintype "passive"))
      (node (ref "C20") (pin "2") (pinfunction "2_2") (pintype "passive"))
      (node (ref "C21") (pin "1") (pinfunction "1_1") (pintype "passive"))
      (node (ref "C23") (pin "2") (pinfunction "2_2") (pintype "passive"))
      (node (ref "C24") (pin "2") (pinfunction "2_2") (pintype "passive"))
      (node (ref "C25") (pin "1") (pinfunction "1_1") (pintype "passive"))
      (node (ref "C27") (pin "2") (pinfunction "2_2") (pintype "passive"))
      (node (ref "C28") (pin "1") (pinfunction "1_1") (pintype "passive"))
      (node (ref "C29") (pin "2") (pinfunction "2_2") (pintype "passive"))
      (node (ref "C3") (pin "1") (pinfunction "1_1") (pintype "passive"))
      (node (ref "C30") (pin "1") (pinfunction "1_1") (pintype "passive"))
      (node (ref "C31") (pin "2") (pinfunction "2_2") (pintype "passive"))
      (node (ref "C4") (pin "1") (pinfunction "1_1") (pintype "passive"))
      (node (ref "C5") (pin "2") (pinfunction "2_2") (pintype "passive"))
      (node (ref "C6") (pin "1") (pinfunction "1_1") (pintype "passive"))
      (node (ref "C7") (pin "1") (pinfunction "1_1") (pintype "passive"))
      (node (ref "C8") (pin "2") (pinfunction "2_2") (pintype "passive"))
      (node (ref "C9") (pin "2") (pinfunction "2_2") (pintype "passive"))
      (node (ref "FB") (pin "P$3") (pinfunction "1_P$3") (pintype "bidirectional"))
      (node (ref "JP1") (pin "GND@1") (pinfunction "GNDBREAK_GND@1") (pintype "bidirectional"))
      (node (ref "JP1") (pin "GND@2") (pinfunction "GND_GND@2") (pintype "bidirectional"))
      (node (ref "JP35") (pin "1") (pinfunction "1_1") (pintype "passive"))
      (node (ref "JP36") (pin "10") (pinfunction "10_10") (pintype "passive"))
      (node (ref "JP36") (pin "4") (pinfunction "4_4") (pintype "passive"))
      (node (ref "JP36") (pin "6") (pinfunction "6_6") (pintype "passive"))
      (node (ref "LED1") (pin "C") (pinfunction "C_C") (pintype "passive"))
      (node (ref "LED10") (pin "C") (pinfunction "C_C") (pintype "passive"))
      (node (ref "LED2") (pin "C") (pinfunction "C_C") (pintype "passive"))
      (node (ref "LED3") (pin "C") (pinfunction "C_C") (pintype "passive"))
      (node (ref "LED4") (pin "C") (pinfunction "C_C") (pintype "passive"))
      (node (ref "LED5") (pin "C") (pinfunction "C_C") (pintype "passive"))
      (node (ref "LED6") (pin "C") (pinfunction "C_C") (pintype "passive"))
      (node (ref "LED7") (pin "C") (pinfunction "C_C") (pintype "passive"))
      (node (ref "LED8") (pin "C") (pinfunction "C_C") (pintype "passive"))
      (node (ref "LED9") (pin "C") (pinfunction "C_C") (pintype "passive"))
      (node (ref "PF5") (pin "3") (pinfunction "3_3") (pintype "passive"))
      (node (ref "PH22") (pin "1") (pinfunction "1_1") (pintype "passive"))
      (node (ref "PH23") (pin "1") (pinfunction "1_1") (pintype "passive"))
      (node (ref "PH24") (pin "1") (pinfunction "1_1") (pintype "passive"))
      (node (ref "PH25") (pin "1") (pinfunction "1_1") (pintype "passive"))
      (node (ref "PH26") (pin "1") (pinfunction "1_1") (pintype "passive"))
      (node (ref "PH28") (pin "3") (pinfunction "3_3") (pintype "passive"))
      (node (ref "PH29") (pin "2") (pinfunction "2_2") (pintype "passive"))
      (node (ref "PH31") (pin "P2") (pinfunction "GND_P2") (pintype "bidirectional"))
      (node (ref "PH34") (pin "6") (pinfunction "6_6") (pintype "passive"))
      (node (ref "PH35") (pin "4") (pinfunction "4_4") (pintype "passive"))
      (node (ref "PH5") (pin "3") (pinfunction "3_3") (pintype "passive"))
      (node (ref "PH6") (pin "3") (pinfunction "3_3") (pintype "passive"))
      (node (ref "R25") (pin "1") (pinfunction "1_1") (pintype "passive"))
      (node (ref "R26") (pin "1") (pinfunction "1_1") (pintype "passive"))
      (node (ref "R28") (pin "1") (pinfunction "1_1") (pintype "passive"))
      (node (ref "R29") (pin "2") (pinfunction "2_2") (pintype "passive"))
      (node (ref "R31") (pin "1") (pinfunction "1_1") (pintype "passive"))
      (node (ref "U$2") (pin "3") (pinfunction "P3_3") (pintype "bidirectional"))
      (node (ref "U$2") (pin "4") (pinfunction "P4_4") (pintype "bidirectional"))
      (node (ref "U$5") (pin "1") (pinfunction "P1_1") (pintype "bidirectional"))
      (node (ref "U$5") (pin "2") (pinfunction "P2_2") (pintype "bidirectional"))
      (node (ref "U$6") (pin "BATM") (pinfunction "P$2_BATM") (pintype "bidirectional"))
      (node (ref "U$7") (pin "6") (pinfunction "VSS_6") (pintype "bidirectional"))
      (node (ref "U$7") (pin "G1") (pinfunction "G1_G1") (pintype "bidirectional"))
      (node (ref "U$7") (pin "G2") (pinfunction "G2_G2") (pintype "bidirectional"))
      (node (ref "U$7") (pin "G3") (pinfunction "G3_G3") (pintype "bidirectional"))
      (node (ref "U$7") (pin "G4") (pinfunction "G4_G4") (pintype "bidirectional"))
      (node (ref "U1") (pin "18") (pinfunction "VSS_4_18") (pintype "bidirectional"))
      (node (ref "U1") (pin "31") (pinfunction "VSS_1_31") (pintype "bidirectional"))
      (node (ref "U1") (pin "47") (pinfunction "VSS_2_47") (pintype "bidirectional"))
      (node (ref "U1") (pin "63") (pinfunction "VSS_3_63") (pintype "bidirectional"))
      (node (ref "U2") (pin "23") (pinfunction "VSS1_23") (pintype "bidirectional"))
      (node (ref "U2") (pin "35") (pinfunction "VSS2_35") (pintype "bidirectional"))
      (node (ref "U2") (pin "44") (pinfunction "BOOT0_44") (pintype "bidirectional"))
      (node (ref "U2") (pin "47") (pinfunction "VSS3_47") (pintype "bidirectional"))
      (node (ref "U2") (pin "8") (pinfunction "VSSA_8") (pintype "bidirectional"))
      (node (ref "U3") (pin "1") (pinfunction "GND_1") (pintype "bidirectional"))
      (node (ref "U5") (pin "1") (pinfunction "GND_1") (pintype "bidirectional"))
      (node (ref "U6") (pin "1") (pinfunction "GND_1") (pintype "bidirectional"))
      (node (ref "U7") (pin "4") (pinfunction "4_4") (pintype "bidirectional"))
      (node (ref "USB1") (pin "GND") (pinfunction "GND_GND") (pintype "bidirectional"))
      (node (ref "USB1") (pin "MTN1") (pinfunction "MTN2_MTN1") (pintype "bidirectional"))
      (node (ref "USB1") (pin "MTN2") (pinfunction "MTN3_MTN2") (pintype "bidirectional"))
      (node (ref "USB1") (pin "MTN3") (pinfunction "MTN1_MTN3") (pintype "bidirectional"))
      (node (ref "USB1") (pin "MTN4") (pinfunction "MTN4_MTN4") (pintype "bidirectional"))
      (node (ref "USB2") (pin "GND") (pinfunction "GND_GND") (pintype "bidirectional"))
      (node (ref "USB2") (pin "MTN1") (pinfunction "MTN2_MTN1") (pintype "bidirectional"))
      (node (ref "USB2") (pin "MTN2") (pinfunction "MTN3_MTN2") (pintype "bidirectional"))
      (node (ref "USB2") (pin "MTN3") (pinfunction "MTN1_MTN3") (pintype "bidirectional"))
      (node (ref "USB2") (pin "MTN4") (pinfunction "MTN4_MTN4") (pintype "bidirectional"))
    )
    (net (code "24") (name "I2C1_SCL") (class "Default")
      (node (ref "PF4") (pin "4") (pinfunction "4_4") (pintype "passive"))
      (node (ref "PF5") (pin "2") (pinfunction "2_2") (pintype "passive"))
      (node (ref "PH18") (pin "1") (pinfunction "1_1") (pintype "bidirectional"))
      (node (ref "PH18") (pin "3") (pinfunction "3_3") (pintype "bidirectional"))
      (node (ref "PH18") (pin "5") (pinfunction "5_5") (pintype "bidirectional"))
      (node (ref "PH4") (pin "4") (pinfunction "4_4") (pintype "passive"))
      (node (ref "PH42") (pin "2") (pinfunction "2_2") (pintype "passive"))
      (node (ref "U1") (pin "58") (pinfunction "PB6_58") (pintype "bidirectional"))
    )
    (net (code "25") (name "I2C1_SDA") (class "Default")
      (node (ref "PF4") (pin "3") (pinfunction "3_3") (pintype "passive"))
      (node (ref "PF5") (pin "1") (pinfunction "1_1") (pintype "passive"))
      (node (ref "PH18") (pin "2") (pinfunction "2_2") (pintype "bidirectional"))
      (node (ref "PH18") (pin "4") (pinfunction "4_4") (pintype "bidirectional"))
      (node (ref "PH18") (pin "6") (pinfunction "6_6") (pintype "bidirectional"))
      (node (ref "PH4") (pin "3") (pinfunction "3_3") (pintype "passive"))
      (node (ref "PH42") (pin "4") (pinfunction "4_4") (pintype "passive"))
      (node (ref "U1") (pin "59") (pinfunction "PB7_59") (pintype "bidirectional"))
    )
    (net (code "26") (name "JNRST") (class "Default")
      (node (ref "PF4") (pin "6") (pinfunction "6_6") (pintype "passive"))
      (node (ref "PH19") (pin "2") (pinfunction "2_2") (pintype "passive"))
      (node (ref "PH20") (pin "2") (pinfunction "2_2") (pintype "passive"))
      (node (ref "PH34") (pin "5") (pinfunction "5_5") (pintype "passive"))
      (node (ref "PH4") (pin "6") (pinfunction "6_6") (pintype "passive"))
      (node (ref "U1") (pin "56") (pinfunction "PB4_56") (pintype "bidirectional"))
    )
    (net (code "27") (name "JTDI") (class "Default")
      (node (ref "PF3") (pin "1") (pinfunction "1_1") (pintype "passive"))
      (node (ref "PH19") (pin "4") (pinfunction "4_4") (pintype "passive"))
      (node (ref "PH21") (pin "3") (pinfunction "3_3") (pintype "passive"))
      (node (ref "PH3") (pin "1") (pinfunction "1_1") (pintype "passive"))
      (node (ref "PH34") (pin "3") (pinfunction "3_3") (pintype "passive"))
      (node (ref "U$16") (pin "P$2") (pinfunction "P$2_P$2") (pintype "bidirectional"))
      (node (ref "U1") (pin "50") (pinfunction "PA15_50") (pintype "bidirectional"))
    )
    (net (code "28") (name "Net-(C4-Pad2)") (class "Default")
      (node (ref "C4") (pin "2") (pinfunction "2_2") (pintype "passive"))
      (node (ref "R1") (pin "1") (pinfunction "1_1") (pintype "passive"))
      (node (ref "USB1") (pin "D-") (pinfunction "D-_D-") (pintype "bidirectional"))
    )
    (net (code "29") (name "Net-(C5-Pad1)") (class "Default")
      (node (ref "C5") (pin "1") (pinfunction "1_1") (pintype "passive"))
      (node (ref "R16") (pin "1") (pinfunction "1_1") (pintype "passive"))
      (node (ref "R2") (pin "1") (pinfunction "1_1") (pintype "passive"))
      (node (ref "USB1") (pin "D+") (pinfunction "D+_D+") (pintype "bidirectional"))
    )
    (net (code "30") (name "Net-(JP1-PadPWR)") (class "Default")
      (node (ref "JP1") (pin "PWR") (pinfunction "PWR_PWR") (pintype "bidirectional"))
      (node (ref "U$25") (pin "ANODE") (pinfunction "ANODE_ANODE") (pintype "bidirectional"))
    )
    (net (code "31") (name "Net-(LED1-PadA)") (class "Default")
      (node (ref "LED1") (pin "A") (pinfunction "A_A") (pintype "passive"))
      (node (ref "R5") (pin "1") (pinfunction "1_1") (pintype "passive"))
    )
    (net (code "32") (name "Net-(LED2-PadA)") (class "Default")
      (node (ref "LED2") (pin "A") (pinfunction "A_A") (pintype "passive"))
      (node (ref "R11") (pin "1") (pinfunction "1_1") (pintype "passive"))
    )
    (net (code "33") (name "Net-(LED3-PadA)") (class "Default")
      (node (ref "LED3") (pin "A") (pinfunction "A_A") (pintype "passive"))
      (node (ref "R6") (pin "1") (pinfunction "1_1") (pintype "passive"))
    )
    (net (code "34") (name "Net-(LED4-PadA)") (class "Default")
      (node (ref "LED4") (pin "A") (pinfunction "A_A") (pintype "passive"))
      (node (ref "R7") (pin "1") (pinfunction "1_1") (pintype "passive"))
    )
    (net (code "35") (name "Net-(LED5-PadA)") (class "Default")
      (node (ref "LED5") (pin "A") (pinfunction "A_A") (pintype "passive"))
      (node (ref "R8") (pin "1") (pinfunction "1_1") (pintype "passive"))
    )
    (net (code "36") (name "Net-(LED6-PadA)") (class "Default")
      (node (ref "LED6") (pin "A") (pinfunction "A_A") (pintype "passive"))
      (node (ref "R12") (pin "1") (pinfunction "1_1") (pintype "passive"))
    )
    (net (code "37") (name "Net-(LED7-PadA)") (class "Default")
      (node (ref "LED7") (pin "A") (pinfunction "A_A") (pintype "passive"))
      (node (ref "R9") (pin "1") (pinfunction "1_1") (pintype "passive"))
    )
    (net (code "38") (name "Net-(LED8-PadA)") (class "Default")
      (node (ref "LED8") (pin "A") (pinfunction "A_A") (pintype "passive"))
      (node (ref "R10") (pin "1") (pinfunction "1_1") (pintype "passive"))
    )
    (net (code "39") (name "Net-(LED9-PadA)") (class "Default")
      (node (ref "LED9") (pin "A") (pinfunction "A_A") (pintype "passive"))
      (node (ref "R13") (pin "1") (pinfunction "1_1") (pintype "passive"))
    )
    (net (code "40") (name "Net-(LED10-PadA)") (class "Default")
      (node (ref "LED10") (pin "A") (pinfunction "A_A") (pintype "passive"))
      (node (ref "R14") (pin "1") (pinfunction "1_1") (pintype "passive"))
    )
    (net (code "41") (name "Net-(PH29-Pad4)") (class "Default")
      (node (ref "PH29") (pin "4") (pinfunction "4_4") (pintype "passive"))
      (node (ref "PH30") (pin "1") (pinfunction "1_1") (pintype "passive"))
    )
    (net (code "42") (name "Net-(PH29-Pad6)") (class "Default")
      (node (ref "PH29") (pin "6") (pinfunction "6_6") (pintype "passive"))
      (node (ref "PH30") (pin "2") (pinfunction "2_2") (pintype "passive"))
    )
    (net (code "43") (name "Net-(PH36-Pad1)") (class "Default")
      (node (ref "PH36") (pin "1") (pinfunction "1_1") (pintype "passive"))
      (node (ref "R20") (pin "1") (pinfunction "1_1") (pintype "passive"))
    )
    (net (code "44") (name "Net-(PH36-Pad3)") (class "Default")
      (node (ref "PH36") (pin "3") (pinfunction "3_3") (pintype "passive"))
      (node (ref "R21") (pin "1") (pinfunction "1_1") (pintype "passive"))
    )
    (net (code "45") (name "Net-(PH40-Pad1)") (class "Default")
      (node (ref "PH40") (pin "1") (pinfunction "1_1") (pintype "passive"))
      (node (ref "R6") (pin "2") (pinfunction "2_2") (pintype "passive"))
    )
    (net (code "46") (name "Net-(PH40-Pad3)") (class "Default")
      (node (ref "PH40") (pin "3") (pinfunction "3_3") (pintype "passive"))
      (node (ref "R7") (pin "2") (pinfunction "2_2") (pintype "passive"))
    )
    (net (code "47") (name "Net-(PH40-Pad5)") (class "Default")
      (node (ref "PH40") (pin "5") (pinfunction "5_5") (pintype "passive"))
      (node (ref "R8") (pin "2") (pinfunction "2_2") (pintype "passive"))
    )
    (net (code "48") (name "Net-(PH42-Pad1)") (class "Default")
      (node (ref "PH42") (pin "1") (pinfunction "1_1") (pintype "passive"))
      (node (ref "R18") (pin "2") (pinfunction "2_2") (pintype "passive"))
    )
    (net (code "49") (name "Net-(PH42-Pad3)") (class "Default")
      (node (ref "PH42") (pin "3") (pinfunction "3_3") (pintype "passive"))
      (node (ref "R19") (pin "2") (pinfunction "2_2") (pintype "passive"))
    )
    (net (code "50") (name "Net-(Q4-2)") (class "Default")
      (node (ref "C3") (pin "2") (pinfunction "2_2") (pintype "passive"))
      (node (ref "Q4") (pin "4") (pinfunction "2_4") (pintype "passive"))
      (node (ref "U1") (pin "3") (pinfunction "PC14-OSC32_IN_3") (pintype "bidirectional"))
    )
    (net (code "51") (name "Net-(R15-Pad2)") (class "Default")
      (node (ref "R15") (pin "2") (pinfunction "2_2") (pintype "passive"))
      (node (ref "R32") (pin "1") (pinfunction "1_1") (pintype "passive"))
      (node (ref "U7") (pin "5") (pinfunction "5_5") (pintype "bidirectional"))
    )
    (net (code "52") (name "Net-(R16-Pad2)") (class "Default")
      (node (ref "R16") (pin "2") (pinfunction "2_2") (pintype "passive"))
      (node (ref "SJ2") (pin "2") (pinfunction "2_2") (pintype "passive"))
      (node (ref "U7") (pin "1") (pinfunction "1_1") (pintype "bidirectional"))
    )
    (net (code "53") (name "Net-(R24-Pad2)") (class "Default")
      (node (ref "R24") (pin "2") (pinfunction "2_2") (pintype "passive"))
      (node (ref "R31") (pin "2") (pinfunction "2_2") (pintype "passive"))
      (node (ref "U7") (pin "2") (pinfunction "2_2") (pintype "bidirectional"))
      (node (ref "U7") (pin "3") (pinfunction "3_3") (pintype "bidirectional"))
    )
    (net (code "54") (name "Net-(U$6-P$1)") (class "Default")
      (node (ref "U$6") (pin "BATP") (pinfunction "P$1_BATP") (pintype "bidirectional"))
      (node (ref "U1") (pin "1") (pinfunction "VBAT_1") (pintype "bidirectional"))
    )
    (net (code "55") (name "Net-(U$8-P3)") (class "Default")
      (node (ref "PH40") (pin "7") (pinfunction "7_7") (pintype "passive"))
      (node (ref "R25") (pin "2") (pinfunction "2_2") (pintype "passive"))
      (node (ref "U$8") (pin "3") (pinfunction "P3_3") (pintype "bidirectional"))
      (node (ref "U$8") (pin "4") (pinfunction "P4_4") (pintype "bidirectional"))
    )
    (net (code "56") (name "Net-(U$9-P3)") (class "Default")
      (node (ref "PH40") (pin "9") (pinfunction "9_9") (pintype "passive"))
      (node (ref "R26") (pin "2") (pinfunction "2_2") (pintype "passive"))
      (node (ref "U$9") (pin "3") (pinfunction "P3_3") (pintype "bidirectional"))
      (node (ref "U$9") (pin "4") (pinfunction "P4_4") (pintype "bidirectional"))
    )
    (net (code "57") (name "Net-(U1-PA2)") (class "Default")
      (node (ref "PF1") (pin "5") (pinfunction "5_5") (pintype "passive"))
      (node (ref "PH1") (pin "5") (pinfunction "5_5") (pintype "passive"))
      (node (ref "PH29") (pin "8") (pinfunction "8_8") (pintype "passive"))
      (node (ref "PH7") (pin "2") (pinfunction "2_2") (pintype "passive"))
      (node (ref "U1") (pin "16") (pinfunction "PA2_16") (pintype "bidirectional"))
    )
    (net (code "58") (name "Net-(U1-PA3)") (class "Default")
      (node (ref "C26") (pin "2") (pinfunction "2_2") (pintype "passive"))
      (node (ref "PF1") (pin "4") (pinfunction "4_4") (pintype "passive"))
      (node (ref "PH1") (pin "4") (pinfunction "4_4") (pintype "passive"))
      (node (ref "PH29") (pin "1") (pinfunction "1_1") (pintype "passive"))
      (node (ref "PH7") (pin "1") (pinfunction "1_1") (pintype "passive"))
      (node (ref "U1") (pin "17") (pinfunction "PA3_17") (pintype "bidirectional"))
    )
    (net (code "59") (name "Net-(U1-PA4)") (class "Default")
      (node (ref "PF1") (pin "3") (pinfunction "3_3") (pintype "passive"))
      (node (ref "PH1") (pin "3") (pinfunction "3_3") (pintype "passive"))
      (node (ref "PH8") (pin "2") (pinfunction "2_2") (pintype "passive"))
      (node (ref "PH9") (pin "4") (pinfunction "4_4") (pintype "passive"))
      (node (ref "U1") (pin "20") (pinfunction "PA4_20") (pintype "bidirectional"))
    )
    (net (code "60") (name "Net-(U1-PA8)") (class "Default")
      (node (ref "PF3") (pin "7") (pinfunction "7_7") (pintype "passive"))
      (node (ref "PH3") (pin "7") (pinfunction "7_7") (pintype "passive"))
      (node (ref "PH40") (pin "10") (pinfunction "10_10") (pintype "passive"))
      (node (ref "U1") (pin "41") (pinfunction "PA8_41") (pintype "bidirectional"))
    )
    (net (code "61") (name "Net-(U1-PB0)") (class "Default")
      (node (ref "PF2") (pin "8") (pinfunction "8_8") (pintype "passive"))
      (node (ref "PH2") (pin "8") (pinfunction "8_8") (pintype "passive"))
      (node (ref "U1") (pin "26") (pinfunction "PB0_26") (pintype "bidirectional"))
    )
    (net (code "62") (name "Net-(U1-PB1)") (class "Default")
      (node (ref "PF2") (pin "7") (pinfunction "7_7") (pintype "passive"))
      (node (ref "PH2") (pin "7") (pinfunction "7_7") (pintype "passive"))
      (node (ref "U1") (pin "27") (pinfunction "PB1_27") (pintype "bidirectional"))
    )
    (net (code "63") (name "Net-(U1-PB5)") (class "Default")
      (node (ref "PF4") (pin "5") (pinfunction "5_5") (pintype "passive"))
      (node (ref "PH19") (pin "1") (pinfunction "1_1") (pintype "passive"))
      (node (ref "PH20") (pin "1") (pinfunction "1_1") (pintype "passive"))
      (node (ref "PH21") (pin "1") (pinfunction "1_1") (pintype "passive"))
      (node (ref "PH4") (pin "5") (pinfunction "5_5") (pintype "passive"))
      (node (ref "U1") (pin "57") (pinfunction "PB5_57") (pintype "bidirectional"))
    )
    (net (code "64") (name "Net-(U1-PB8)") (class "Default")
      (node (ref "PF4") (pin "2") (pinfunction "2_2") (pintype "passive"))
      (node (ref "PH4") (pin "2") (pinfunction "2_2") (pintype "passive"))
      (node (ref "U1") (pin "61") (pinfunction "PB8_61") (pintype "bidirectional"))
    )
    (net (code "65") (name "Net-(U1-PB9)") (class "Default")
      (node (ref "PF4") (pin "1") (pinfunction "1_1") (pintype "passive"))
      (node (ref "PH4") (pin "1") (pinfunction "1_1") (pintype "passive"))
      (node (ref "U1") (pin "62") (pinfunction "PB9_62") (pintype "bidirectional"))
    )
    (net (code "66") (name "Net-(U1-PB10)") (class "Default")
      (node (ref "PF2") (pin "6") (pinfunction "6_6") (pintype "passive"))
      (node (ref "PH2") (pin "6") (pinfunction "6_6") (pintype "passive"))
      (node (ref "PH36") (pin "2") (pinfunction "2_2") (pintype "passive"))
      (node (ref "PH37") (pin "2") (pinfunction "2_2") (pintype "passive"))
      (node (ref "PH38") (pin "2") (pinfunction "2_2") (pintype "passive"))
      (node (ref "U1") (pin "29") (pinfunction "PB10_29") (pintype "bidirectional"))
    )
    (net (code "67") (name "Net-(U1-PB11)") (class "Default")
      (node (ref "PF2") (pin "5") (pinfunction "5_5") (pintype "passive"))
      (node (ref "PH2") (pin "5") (pinfunction "5_5") (pintype "passive"))
      (node (ref "PH36") (pin "4") (pinfunction "4_4") (pintype "passive"))
      (node (ref "PH37") (pin "1") (pinfunction "1_1") (pintype "passive"))
      (node (ref "PH38") (pin "1") (pinfunction "1_1") (pintype "passive"))
      (node (ref "U1") (pin "30") (pinfunction "PB11_30") (pintype "bidirectional"))
    )
    (net (code "68") (name "Net-(U1-PB12)") (class "Default")
      (node (ref "PF2") (pin "4") (pinfunction "4_4") (pintype "passive"))
      (node (ref "PH12") (pin "4") (pinfunction "4_4") (pintype "passive"))
      (node (ref "PH14") (pin "4") (pinfunction "4_4") (pintype "passive"))
      (node (ref "PH2") (pin "4") (pinfunction "4_4") (pintype "passive"))
      (node (ref "PH39") (pin "7") (pinfunction "7_7") (pintype "passive"))
      (node (ref "U1") (pin "33") (pinfunction "PB12_33") (pintype "bidirectional"))
    )
    (net (code "69") (name "Net-(U1-PB13)") (class "Default")
      (node (ref "PF2") (pin "3") (pinfunction "3_3") (pintype "passive"))
      (node (ref "PH12") (pin "3") (pinfunction "3_3") (pintype "passive"))
      (node (ref "PH13") (pin "3") (pinfunction "3_3") (pintype "passive"))
      (node (ref "PH14") (pin "3") (pinfunction "3_3") (pintype "passive"))
      (node (ref "PH2") (pin "3") (pinfunction "3_3") (pintype "passive"))
      (node (ref "PH39") (pin "5") (pinfunction "5_5") (pintype "passive"))
      (node (ref "U1") (pin "34") (pinfunction "PB13_34") (pintype "bidirectional"))
    )
    (net (code "70") (name "Net-(U1-PB14)") (class "Default")
      (node (ref "PF2") (pin "2") (pinfunction "2_2") (pintype "passive"))
      (node (ref "PH12") (pin "2") (pinfunction "2_2") (pintype "passive"))
      (node (ref "PH13") (pin "2") (pinfunction "2_2") (pintype "passive"))
      (node (ref "PH2") (pin "2") (pinfunction "2_2") (pintype "passive"))
      (node (ref "PH39") (pin "3") (pinfunction "3_3") (pintype "passive"))
      (node (ref "U1") (pin "35") (pinfunction "PB14_35") (pintype "bidirectional"))
    )
    (net (code "71") (name "Net-(U1-PB15)") (class "Default")
      (node (ref "PF2") (pin "1") (pinfunction "1_1") (pintype "passive"))
      (node (ref "PH12") (pin "1") (pinfunction "1_1") (pintype "passive"))
      (node (ref "PH13") (pin "1") (pinfunction "1_1") (pintype "passive"))
      (node (ref "PH14") (pin "2") (pinfunction "2_2") (pintype "passive"))
      (node (ref "PH2") (pin "1") (pinfunction "1_1") (pintype "passive"))
      (node (ref "PH39") (pin "1") (pinfunction "1_1") (pintype "passive"))
      (node (ref "U1") (pin "36") (pinfunction "PB15_36") (pintype "bidirectional"))
    )
    (net (code "72") (name "Net-(U1-PC0)") (class "Default")
      (node (ref "PF1") (pin "11") (pinfunction "11_11") (pintype "passive"))
      (node (ref "PH1") (pin "11") (pinfunction "11_11") (pintype "passive"))
      (node (ref "U1") (pin "8") (pinfunction "PC0_8") (pintype "bidirectional"))
    )
    (net (code "73") (name "Net-(U1-PC1)") (class "Default")
      (node (ref "PF1") (pin "10") (pinfunction "10_10") (pintype "passive"))
      (node (ref "PH1") (pin "10") (pinfunction "10_10") (pintype "passive"))
      (node (ref "U1") (pin "9") (pinfunction "PC1_9") (pintype "bidirectional"))
    )
    (net (code "74") (name "Net-(U1-PC2)") (class "Default")
      (node (ref "PF1") (pin "9") (pinfunction "9_9") (pintype "passive"))
      (node (ref "PH1") (pin "9") (pinfunction "9_9") (pintype "passive"))
      (node (ref "U1") (pin "10") (pinfunction "PC2_10") (pintype "bidirectional"))
    )
    (net (code "75") (name "Net-(U1-PC3)") (class "Default")
      (node (ref "PF1") (pin "8") (pinfunction "8_8") (pintype "passive"))
      (node (ref "PH1") (pin "8") (pinfunction "8_8") (pintype "passive"))
      (node (ref "U1") (pin "11") (pinfunction "PC3_11") (pintype "bidirectional"))
    )
    (net (code "76") (name "Net-(U1-PC4)") (class "Default")
      (node (ref "PF2") (pin "10") (pinfunction "10_10") (pintype "passive"))
      (node (ref "PH2") (pin "10") (pinfunction "10_10") (pintype "passive"))
      (node (ref "U1") (pin "24") (pinfunction "PC4_24") (pintype "bidirectional"))
    )
    (net (code "77") (name "Net-(U1-PC5)") (class "Default")
      (node (ref "PF2") (pin "9") (pinfunction "9_9") (pintype "passive"))
      (node (ref "PH2") (pin "9") (pinfunction "9_9") (pintype "passive"))
      (node (ref "U1") (pin "25") (pinfunction "PC5_25") (pintype "bidirectional"))
    )
    (net (code "78") (name "Net-(U1-PC6)") (class "Default")
      (node (ref "PF3") (pin "11") (pinfunction "11_11") (pintype "passive"))
      (node (ref "PH14") (pin "1") (pinfunction "1_1") (pintype "passive"))
      (node (ref "PH3") (pin "11") (pinfunction "11_11") (pintype "passive"))
      (node (ref "PH40") (pin "2") (pinfunction "2_2") (pintype "passive"))
      (node (ref "U1") (pin "37") (pinfunction "PC6_37") (pintype "bidirectional"))
    )
    (net (code "79") (name "Net-(U1-PC7)") (class "Default")
      (node (ref "PF3") (pin "10") (pinfunction "10_10") (pintype "passive"))
      (node (ref "PH21") (pin "4") (pinfunction "4_4") (pintype "passive"))
      (node (ref "PH3") (pin "10") (pinfunction "10_10") (pintype "passive"))
      (node (ref "PH40") (pin "4") (pinfunction "4_4") (pintype "passive"))
      (node (ref "U1") (pin "38") (pinfunction "PC7_38") (pintype "bidirectional"))
    )
    (net (code "80") (name "Net-(U1-PC8)") (class "Default")
      (node (ref "PF3") (pin "9") (pinfunction "9_9") (pintype "passive"))
      (node (ref "PH3") (pin "9") (pinfunction "9_9") (pintype "passive"))
      (node (ref "PH40") (pin "6") (pinfunction "6_6") (pintype "passive"))
      (node (ref "U1") (pin "39") (pinfunction "PC8_39") (pintype "bidirectional"))
    )
    (net (code "81") (name "Net-(U1-PC9)") (class "Default")
      (node (ref "PF3") (pin "8") (pinfunction "8_8") (pintype "passive"))
      (node (ref "PH3") (pin "8") (pinfunction "8_8") (pintype "passive"))
      (node (ref "PH40") (pin "8") (pinfunction "8_8") (pintype "passive"))
      (node (ref "U1") (pin "40") (pinfunction "PC9_40") (pintype "bidirectional"))
    )
    (net (code "82") (name "Net-(U1-PC10)") (class "Default")
      (node (ref "PF4") (pin "10") (pinfunction "10_10") (pintype "passive"))
      (node (ref "PH17") (pin "2") (pinfunction "2_2") (pintype "passive"))
      (node (ref "PH4") (pin "10") (pinfunction "10_10") (pintype "passive"))
      (node (ref "PH41") (pin "5") (pinfunction "5_5") (pintype "passive"))
      (node (ref "U1") (pin "51") (pinfunction "PC10_51") (pintype "bidirectional"))
    )
    (net (code "83") (name "Net-(U1-PC11)") (class "Default")
      (node (ref "PF4") (pin "9") (pinfunction "9_9") (pintype "passive"))
      (node (ref "PH17") (pin "1") (pinfunction "1_1") (pintype "passive"))
      (node (ref "PH4") (pin "9") (pinfunction "9_9") (pintype "passive"))
      (node (ref "PH41") (pin "3") (pinfunction "3_3") (pintype "passive"))
      (node (ref "U1") (pin "52") (pinfunction "PC11_52") (pintype "bidirectional"))
    )
    (net (code "84") (name "Net-(U1-PC15-OSC32_OUT)") (class "Default")
      (node (ref "C2") (pin "2") (pinfunction "2_2") (pintype "passive"))
      (node (ref "Q4") (pin "1") (pinfunction "1_1") (pintype "passive"))
      (node (ref "U1") (pin "4") (pinfunction "PC15-OSC32_OUT_4") (pintype "bidirectional"))
    )
    (net (code "85") (name "Net-(U1-PD0-OSC_IN)") (class "Default")
      (node (ref "C28") (pin "2") (pinfunction "2_2") (pintype "passive"))
      (node (ref "Q3") (pin "2") (pinfunction "2_2") (pintype "passive"))
      (node (ref "U1") (pin "5") (pinfunction "PD0-OSC_IN_5") (pintype "bidirectional"))
    )
    (net (code "86") (name "Net-(U1-PD1-OSC_OUT)") (class "Default")
      (node (ref "C29") (pin "1") (pinfunction "1_1") (pintype "passive"))
      (node (ref "Q3") (pin "1") (pinfunction "1_1") (pintype "passive"))
      (node (ref "U1") (pin "6") (pinfunction "PD1-OSC_OUT_6") (pintype "bidirectional"))
    )
    (net (code "87") (name "Net-(U1-PD2)") (class "Default")
      (node (ref "PF4") (pin "8") (pinfunction "8_8") (pintype "passive"))
      (node (ref "PH4") (pin "8") (pinfunction "8_8") (pintype "passive"))
      (node (ref "U1") (pin "54") (pinfunction "PD2_54") (pintype "bidirectional"))
    )
    (net (code "88") (name "Net-(U2-OSC_IN)") (class "Default")
      (node (ref "C30") (pin "2") (pinfunction "2_2") (pintype "passive"))
      (node (ref "Q2") (pin "2") (pinfunction "2_2") (pintype "passive"))
      (node (ref "U2") (pin "5") (pinfunction "OSC_IN_5") (pintype "bidirectional"))
    )
    (net (code "89") (name "Net-(U2-OSC_OUT)") (class "Default")
      (node (ref "C31") (pin "1") (pinfunction "1_1") (pintype "passive"))
      (node (ref "Q2") (pin "1") (pinfunction "1_1") (pintype "passive"))
      (node (ref "U2") (pin "6") (pinfunction "OSC_OUT_6") (pintype "bidirectional"))
    )
    (net (code "90") (name "Net-(U2-PA8)") (class "Default")
      (node (ref "R17") (pin "1") (pinfunction "1_1") (pintype "passive"))
      (node (ref "U2") (pin "29") (pinfunction "PA8_29") (pintype "bidirectional"))
    )
    (net (code "91") (name "Net-(U2-PB0)") (class "Default")
      (node (ref "C16") (pin "2") (pinfunction "2_2") (pintype "passive"))
      (node (ref "R22") (pin "1") (pinfunction "1_1") (pintype "passive"))
      (node (ref "R28") (pin "2") (pinfunction "2_2") (pintype "passive"))
      (node (ref "U2") (pin "18") (pinfunction "PB0_18") (pintype "bidirectional"))
    )
    (net (code "92") (name "Net-(U3-VIN)") (class "Default")
      (node (ref "C11") (pin "2") (pinfunction "2_2") (pintype "passive"))
      (node (ref "C13") (pin "2") (pinfunction "2_2") (pintype "passive"))
      (node (ref "PH43") (pin "2") (pinfunction "2_2") (pintype "passive"))
      (node (ref "U3") (pin "3") (pinfunction "VIN_3") (pintype "bidirectional"))
      (node (ref "U4") (pin "3") (pinfunction "VIN_3") (pintype "bidirectional"))
    )
    (net (code "93") (name "Net-(U8-B)") (class "Default")
      (node (ref "PH33") (pin "2") (pinfunction "2_2") (pintype "passive"))
      (node (ref "U8") (pin "1") (pinfunction "B_1") (pintype "bidirectional"))
    )
    (net (code "94") (name "PC13") (class "Default")
      (node (ref "PF1") (pin "12") (pinfunction "12_12") (pintype "passive"))
      (node (ref "PH1") (pin "12") (pinfunction "12_12") (pintype "passive"))
      (node (ref "U1") (pin "2") (pinfunction "PC13-TAMPER-RTC_2") (pintype "bidirectional"))
    )
    (net (code "95") (name "PWR_BR") (class "Default")
      (node (ref "U2") (pin "19") (pinfunction "PB1_19") (pintype "bidirectional"))
      (node (ref "U9") (pin "1") (pinfunction "G_1") (pintype "bidirectional"))
    )
    (net (code "96") (name "RST") (class "Default")
      (node (ref "C14") (pin "2") (pinfunction "2_2") (pintype "passive"))
      (node (ref "PH35") (pin "2") (pinfunction "2_2") (pintype "passive"))
      (node (ref "U$15") (pin "P$2") (pinfunction "P$2_P$2") (pintype "bidirectional"))
      (node (ref "U$5") (pin "3") (pinfunction "P3_3") (pintype "bidirectional"))
      (node (ref "U$5") (pin "4") (pinfunction "P4_4") (pintype "bidirectional"))
      (node (ref "U1") (pin "7") (pinfunction "NRST_7") (pintype "bidirectional"))
    )
    (net (code "97") (name "SD_CD") (class "Default")
      (node (ref "R27") (pin "1") (pinfunction "1_1") (pintype "passive"))
      (node (ref "U$7") (pin "CD") (pinfunction "CARD_CD") (pintype "bidirectional"))
    )
    (net (code "98") (name "SD_CS") (class "Default")
      (node (ref "PF1") (pin "6") (pinfunction "6_6") (pintype "passive"))
      (node (ref "PH1") (pin "6") (pinfunction "6_6") (pintype "passive"))
      (node (ref "PH39") (pin "6") (pinfunction "6_6") (pintype "passive"))
      (node (ref "U$7") (pin "2") (pinfunction "CD/DAT3_2") (pintype "bidirectional"))
      (node (ref "U1") (pin "15") (pinfunction "PA1_15") (pintype "bidirectional"))
    )
    (net (code "99") (name "SD_DC") (class "Default")
      (node (ref "PF1") (pin "7") (pinfunction "7_7") (pintype "passive"))
      (node (ref "PH1") (pin "7") (pinfunction "7_7") (pintype "passive"))
      (node (ref "U1") (pin "14") (pinfunction "PA0-WKUP_14") (pintype "bidirectional"))
    )
    (net (code "100") (name "SPI1_MISO") (class "Default")
      (node (ref "PF1") (pin "1") (pinfunction "1_1") (pintype "passive"))
      (node (ref "PH1") (pin "1") (pinfunction "1_1") (pintype "passive"))
      (node (ref "PH10") (pin "2") (pinfunction "2_2") (pintype "passive"))
      (node (ref "PH11") (pin "2") (pinfunction "2_2") (pintype "passive"))
      (node (ref "PH31") (pin "P13") (pinfunction "T_DO_P13") (pintype "bidirectional"))
      (node (ref "PH31") (pin "P9") (pinfunction "MISO_P9") (pintype "bidirectional"))
      (node (ref "PH9") (pin "2") (pinfunction "2_2") (pintype "passive"))
      (node (ref "U$7") (pin "7") (pinfunction "DAT0_7") (pintype "bidirectional"))
      (node (ref "U1") (pin "22") (pinfunction "PA6_22") (pintype "bidirectional"))
    )
    (net (code "101") (name "SPI1_MOSI") (class "Default")
      (node (ref "PF2") (pin "11") (pinfunction "11_11") (pintype "passive"))
      (node (ref "PH10") (pin "1") (pinfunction "1_1") (pintype "passive"))
      (node (ref "PH11") (pin "1") (pinfunction "1_1") (pintype "passive"))
      (node (ref "PH2") (pin "11") (pinfunction "11_11") (pintype "passive"))
      (node (ref "PH31") (pin "P12") (pinfunction "T_DIN_P12") (pintype "bidirectional"))
      (node (ref "PH31") (pin "P6") (pinfunction "MOSI_P6") (pintype "bidirectional"))
      (node (ref "PH9") (pin "1") (pinfunction "1_1") (pintype "passive"))
      (node (ref "U$7") (pin "3") (pinfunction "CMD_3") (pintype "bidirectional"))
      (node (ref "U1") (pin "23") (pinfunction "PA7_23") (pintype "bidirectional"))
    )
    (net (code "102") (name "SPI1_SCK") (class "Default")
      (node (ref "PF1") (pin "2") (pinfunction "2_2") (pintype "passive"))
      (node (ref "PH1") (pin "2") (pinfunction "2_2") (pintype "passive"))
      (node (ref "PH10") (pin "3") (pinfunction "3_3") (pintype "passive"))
      (node (ref "PH11") (pin "3") (pinfunction "3_3") (pintype "passive"))
      (node (ref "PH31") (pin "P10") (pinfunction "T_CLK_P10") (pintype "bidirectional"))
      (node (ref "PH31") (pin "P7") (pinfunction "SCK_P7") (pintype "bidirectional"))
      (node (ref "PH8") (pin "1") (pinfunction "1_1") (pintype "passive"))
      (node (ref "PH9") (pin "3") (pinfunction "3_3") (pintype "passive"))
      (node (ref "U$7") (pin "5") (pinfunction "CLK_5") (pintype "bidirectional"))
      (node (ref "U1") (pin "21") (pinfunction "PA5_21") (pintype "bidirectional"))
    )
    (net (code "103") (name "SRX") (class "Default")
      (node (ref "PF3") (pin "6") (pinfunction "6_6") (pintype "passive"))
      (node (ref "PH15") (pin "2") (pinfunction "2_2") (pintype "passive"))
      (node (ref "PH3") (pin "6") (pinfunction "6_6") (pintype "passive"))
      (node (ref "U$4") (pin "P$2") (pinfunction "P$2_P$2") (pintype "bidirectional"))
      (node (ref "U1") (pin "42") (pinfunction "PA9_42") (pintype "bidirectional"))
    )
    (net (code "104") (name "STX") (class "Default")
      (node (ref "PF3") (pin "5") (pinfunction "5_5") (pintype "passive"))
      (node (ref "PH15") (pin "1") (pinfunction "1_1") (pintype "passive"))
      (node (ref "PH3") (pin "5") (pinfunction "5_5") (pintype "passive"))
      (node (ref "U$1") (pin "P$2") (pinfunction "P$2_P$2") (pintype "bidirectional"))
      (node (ref "U1") (pin "43") (pinfunction "PA10_43") (pintype "bidirectional"))
    )
    (net (code "105") (name "SWCLK") (class "Default")
      (node (ref "PF3") (pin "2") (pinfunction "2_2") (pintype "passive"))
      (node (ref "PH3") (pin "2") (pinfunction "2_2") (pintype "passive"))
      (node (ref "PH34") (pin "2") (pinfunction "2_2") (pintype "passive"))
      (node (ref "PH35") (pin "5") (pinfunction "5_5") (pintype "passive"))
      (node (ref "U$18") (pin "P$2") (pinfunction "P$2_P$2") (pintype "bidirectional"))
      (node (ref "U1") (pin "49") (pinfunction "PA14_49") (pintype "bidirectional"))
    )
    (net (code "106") (name "SWDIO") (class "Default")
      (node (ref "PH34") (pin "1") (pinfunction "1_1") (pintype "passive"))
      (node (ref "PH35") (pin "3") (pinfunction "3_3") (pintype "passive"))
      (node (ref "U$19") (pin "P$2") (pinfunction "P$2_P$2") (pintype "bidirectional"))
      (node (ref "U1") (pin "46") (pinfunction "PA13_46") (pintype "bidirectional"))
    )
    (net (code "107") (name "SWO") (class "Default")
      (node (ref "PF4") (pin "7") (pinfunction "7_7") (pintype "passive"))
      (node (ref "PH19") (pin "3") (pinfunction "3_3") (pintype "passive"))
      (node (ref "PH20") (pin "3") (pinfunction "3_3") (pintype "passive"))
      (node (ref "PH21") (pin "2") (pinfunction "2_2") (pintype "passive"))
      (node (ref "PH34") (pin "4") (pinfunction "4_4") (pintype "passive"))
      (node (ref "PH35") (pin "1") (pinfunction "1_1") (pintype "passive"))
      (node (ref "PH4") (pin "7") (pinfunction "7_7") (pintype "passive"))
      (node (ref "PH41") (pin "1") (pinfunction "1_1") (pintype "passive"))
      (node (ref "U$17") (pin "P$2") (pinfunction "P$2_P$2") (pintype "bidirectional"))
      (node (ref "U1") (pin "55") (pinfunction "PB3_55") (pintype "bidirectional"))
    )
    (net (code "108") (name "TFT_CS") (class "Default")
      (node (ref "PH31") (pin "P3") (pinfunction "CS_P3") (pintype "bidirectional"))
      (node (ref "PH39") (pin "4") (pinfunction "4_4") (pintype "passive"))
    )
    (net (code "109") (name "TFT_DC") (class "Default")
      (node (ref "PH31") (pin "P5") (pinfunction "DC_P5") (pintype "bidirectional"))
      (node (ref "PH41") (pin "4") (pinfunction "4_4") (pintype "passive"))
    )
    (net (code "110") (name "TFT_LED") (class "Default")
      (node (ref "PH31") (pin "P8") (pinfunction "LED_P8") (pintype "bidirectional"))
      (node (ref "PH32") (pin "1") (pinfunction "1_1") (pintype "passive"))
      (node (ref "U8") (pin "2") (pinfunction "E_2") (pintype "bidirectional"))
    )
    (net (code "111") (name "TFT_LED_B") (class "Default")
      (node (ref "PH33") (pin "1") (pinfunction "1_1") (pintype "passive"))
      (node (ref "PH39") (pin "8") (pinfunction "8_8") (pintype "passive"))
    )
    (net (code "112") (name "TFT_RST") (class "Default")
      (node (ref "PH31") (pin "P4") (pinfunction "RESET_P4") (pintype "bidirectional"))
      (node (ref "PH41") (pin "6") (pinfunction "6_6") (pintype "passive"))
    )
    (net (code "113") (name "TFT_TOUCH_CS") (class "Default")
      (node (ref "PH31") (pin "P11") (pinfunction "T_CS_P11") (pintype "bidirectional"))
      (node (ref "PH39") (pin "2") (pinfunction "2_2") (pintype "passive"))
    )
    (net (code "114") (name "TFT_TOUCH_INTERRUPT") (class "Default")
      (node (ref "PH31") (pin "P14") (pinfunction "T_IRQ_P14") (pintype "bidirectional"))
      (node (ref "PH41") (pin "2") (pinfunction "2_2") (pintype "passive"))
    )
    (net (code "115") (name "TPWR") (class "Default")
      (node (ref "JP36") (pin "2") (pinfunction "2_2") (pintype "passive"))
      (node (ref "R22") (pin "2") (pinfunction "2_2") (pintype "passive"))
      (node (ref "U$10") (pin "P$1") (pinfunction "P$1_P$1") (pintype "bidirectional"))
      (node (ref "U9") (pin "3") (pinfunction "D_3") (pintype "bidirectional"))
    )
    (net (code "116") (name "USBDM") (class "Default")
      (node (ref "PF3") (pin "4") (pinfunction "4_4") (pintype "passive"))
      (node (ref "PH16") (pin "2") (pinfunction "2_2") (pintype "passive"))
      (node (ref "PH3") (pin "4") (pinfunction "4_4") (pintype "passive"))
      (node (ref "R1") (pin "2") (pinfunction "2_2") (pintype "passive"))
      (node (ref "R10") (pin "2") (pinfunction "2_2") (pintype "passive"))
      (node (ref "U1") (pin "44") (pinfunction "PA11_44") (pintype "bidirectional"))
    )
    (net (code "117") (name "USBDP") (class "Default")
      (node (ref "PF3") (pin "3") (pinfunction "3_3") (pintype "passive"))
      (node (ref "PH16") (pin "1") (pinfunction "1_1") (pintype "passive"))
      (node (ref "PH3") (pin "3") (pinfunction "3_3") (pintype "passive"))
      (node (ref "R2") (pin "2") (pinfunction "2_2") (pintype "passive"))
      (node (ref "R9") (pin "2") (pinfunction "2_2") (pintype "passive"))
      (node (ref "U1") (pin "45") (pinfunction "PA12_45") (pintype "bidirectional"))
    )
    (net (code "118") (name "VBUS") (class "Default")
      (node (ref "R23") (pin "1") (pinfunction "1_1") (pintype "passive"))
      (node (ref "R29") (pin "1") (pinfunction "1_1") (pintype "passive"))
      (node (ref "U2") (pin "26") (pinfunction "PB13_26") (pintype "bidirectional"))
    )
    (net (code "119") (name "VDD") (class "Default")
      (node (ref "C1") (pin "2") (pinfunction "2_2") (pintype "passive"))
      (node (ref "C12") (pin "1") (pinfunction "1_1") (pintype "passive"))
      (node (ref "C22") (pin "2") (pinfunction "2_2") (pintype "passive"))
      (node (ref "PH44") (pin "1") (pinfunction "1_1") (pintype "passive"))
      (node (ref "PH44") (pin "3") (pinfunction "3_3") (pintype "passive"))
      (node (ref "SJ1") (pin "1") (pinfunction "1_1") (pintype "passive"))
      (node (ref "U1") (pin "13") (pinfunction "VDDA_13") (pintype "bidirectional"))
      (node (ref "U4") (pin "2") (pinfunction "VOUT_2") (pintype "bidirectional"))
    )
    (net (code "120") (name "VIN") (class "Default")
      (node (ref "C25") (pin "2") (pinfunction "2_2") (pintype "passive"))
      (node (ref "PH27") (pin "1") (pinfunction "1_1") (pintype "passive"))
      (node (ref "PH27") (pin "2") (pinfunction "2_2") (pintype "passive"))
      (node (ref "PH43") (pin "3") (pinfunction "3_3") (pintype "passive"))
      (node (ref "U$25") (pin "CATHODE") (pinfunction "CATHODE_CATHODE") (pintype "bidirectional"))
      (node (ref "U5") (pin "3") (pinfunction "VIN_3") (pintype "bidirectional"))
    )
    (net (code "121") (name "unconnected-(JP36-Pad8)") (class "Default")
      (node (ref "JP36") (pin "8") (pinfunction "8_8") (pintype "passive"))
    )
    (net (code "122") (name "unconnected-(U$7-DAT1-Pad8)") (class "Default")
      (node (ref "U$7") (pin "8") (pinfunction "DAT1_8") (pintype "bidirectional"))
    )
    (net (code "123") (name "unconnected-(U$7-DAT2-Pad1)") (class "Default")
      (node (ref "U$7") (pin "1") (pinfunction "DAT2_1") (pintype "bidirectional"))
    )
    (net (code "124") (name "unconnected-(U2-NRST-Pad7)") (class "Default")
      (node (ref "U2") (pin "7") (pinfunction "NRST_7") (pintype "bidirectional"))
    )
    (net (code "125") (name "unconnected-(U2-PA0-Pad10)") (class "Default")
      (node (ref "U2") (pin "10") (pinfunction "PA0_10") (pintype "bidirectional"))
    )
    (net (code "126") (name "unconnected-(U2-PA1-Pad11)") (class "Default")
      (node (ref "U2") (pin "11") (pinfunction "PA1_11") (pintype "bidirectional"))
    )
    (net (code "127") (name "unconnected-(U2-PA7-Pad17)") (class "Default")
      (node (ref "U2") (pin "17") (pinfunction "PA7_17") (pintype "bidirectional"))
    )
    (net (code "128") (name "unconnected-(U2-PA15-Pad38)") (class "Default")
      (node (ref "U2") (pin "38") (pinfunction "PA15_38") (pintype "bidirectional"))
    )
    (net (code "129") (name "unconnected-(U2-PB3-Pad39)") (class "Default")
      (node (ref "U2") (pin "39") (pinfunction "PB3_39") (pintype "bidirectional"))
    )
    (net (code "130") (name "unconnected-(U2-PB4-Pad40)") (class "Default")
      (node (ref "U2") (pin "40") (pinfunction "PB4_40") (pintype "bidirectional"))
    )
    (net (code "131") (name "unconnected-(U2-PB5-Pad41)") (class "Default")
      (node (ref "U2") (pin "41") (pinfunction "PB5_41") (pintype "bidirectional"))
    )
    (net (code "132") (name "unconnected-(U2-PB6-Pad42)") (class "Default")
      (node (ref "U2") (pin "42") (pinfunction "PB6_42") (pintype "bidirectional"))
    )
    (net (code "133") (name "unconnected-(U2-PB7-Pad43)") (class "Default")
      (node (ref "U2") (pin "43") (pinfunction "PB7_43") (pintype "bidirectional"))
    )
    (net (code "134") (name "unconnected-(U2-PB8-Pad45)") (class "Default")
      (node (ref "U2") (pin "45") (pinfunction "PB8_45") (pintype "bidirectional"))
    )
    (net (code "135") (name "unconnected-(U2-PB9-Pad46)") (class "Default")
      (node (ref "U2") (pin "46") (pinfunction "PB9_46") (pintype "bidirectional"))
    )
    (net (code "136") (name "unconnected-(U2-PB14-Pad27)") (class "Default")
      (node (ref "U2") (pin "27") (pinfunction "PB14_27") (pintype "bidirectional"))
    )
    (net (code "137") (name "unconnected-(U2-PB15-Pad28)") (class "Default")
      (node (ref "U2") (pin "28") (pinfunction "PB15_28") (pintype "bidirectional"))
    )
    (net (code "138") (name "unconnected-(U2-PC13-TAMPER-RTC-Pad2)") (class "Default")
      (node (ref "U2") (pin "2") (pinfunction "PC13-TAMPER-RTC_2") (pintype "bidirectional"))
    )
    (net (code "139") (name "unconnected-(U2-PC14-OSC32_IN-Pad3)") (class "Default")
      (node (ref "U2") (pin "3") (pinfunction "PC14-OSC32_IN_3") (pintype "bidirectional"))
    )
    (net (code "140") (name "unconnected-(U2-PC15-OSC32_OUT-Pad4)") (class "Default")
      (node (ref "U2") (pin "4") (pinfunction "PC15-OSC32_OUT_4") (pintype "bidirectional"))
    )
    (net (code "141") (name "unconnected-(USB1-PadID)") (class "Default")
      (node (ref "USB1") (pin "ID") (pinfunction "ID_ID") (pintype "bidirectional"))
    )
    (net (code "142") (name "unconnected-(USB2-PadID)") (class "Default")
      (node (ref "USB2") (pin "ID") (pinfunction "ID_ID") (pintype "bidirectional"))
    )
  )
)
